# KON-SU260.net
KiCad netlist of a schematic drawn in EAGLE
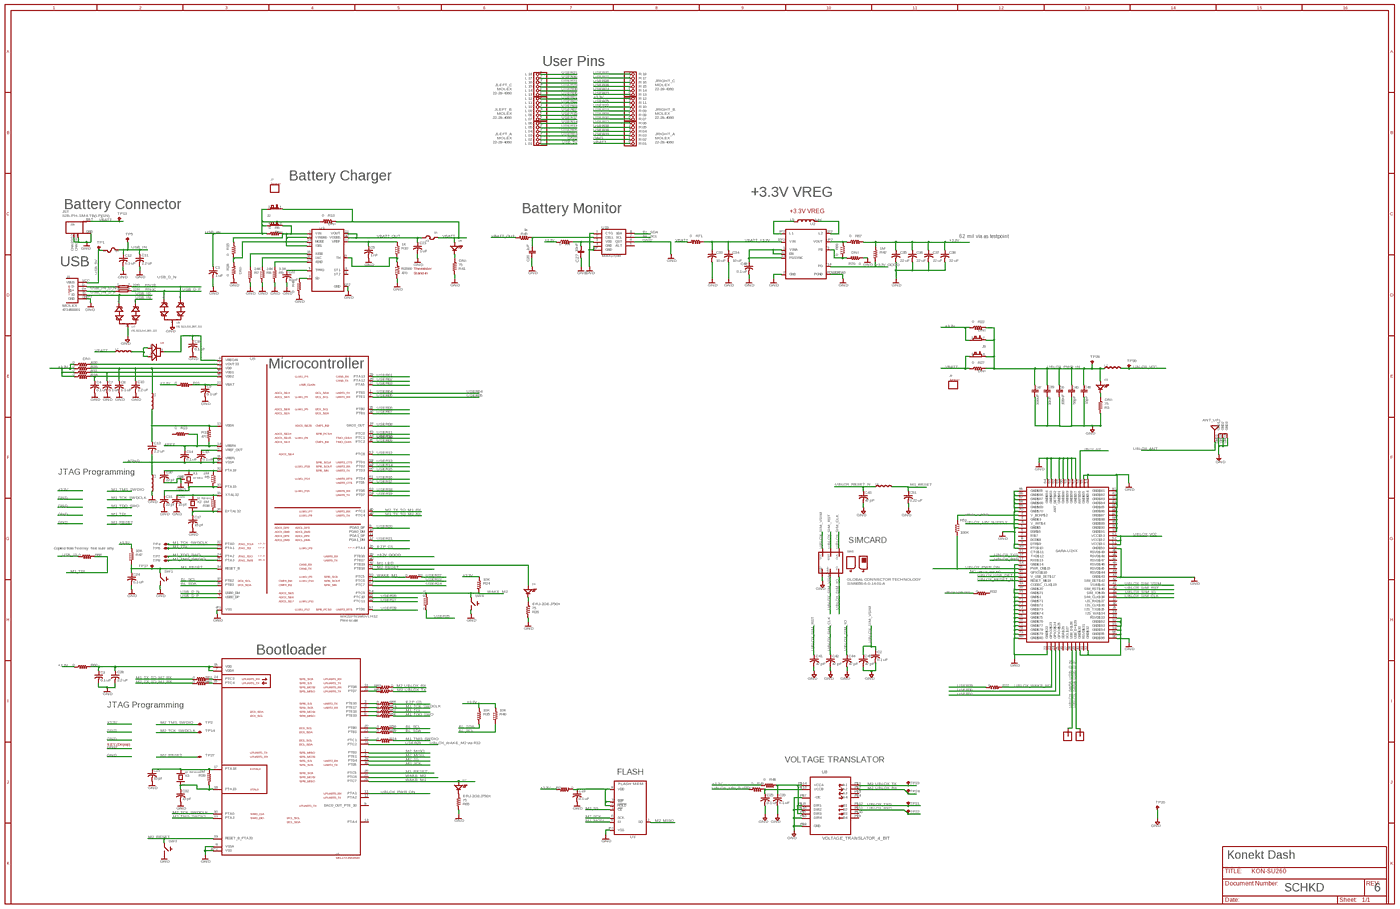
[diagram p0: schematic, sheet 1, overview]
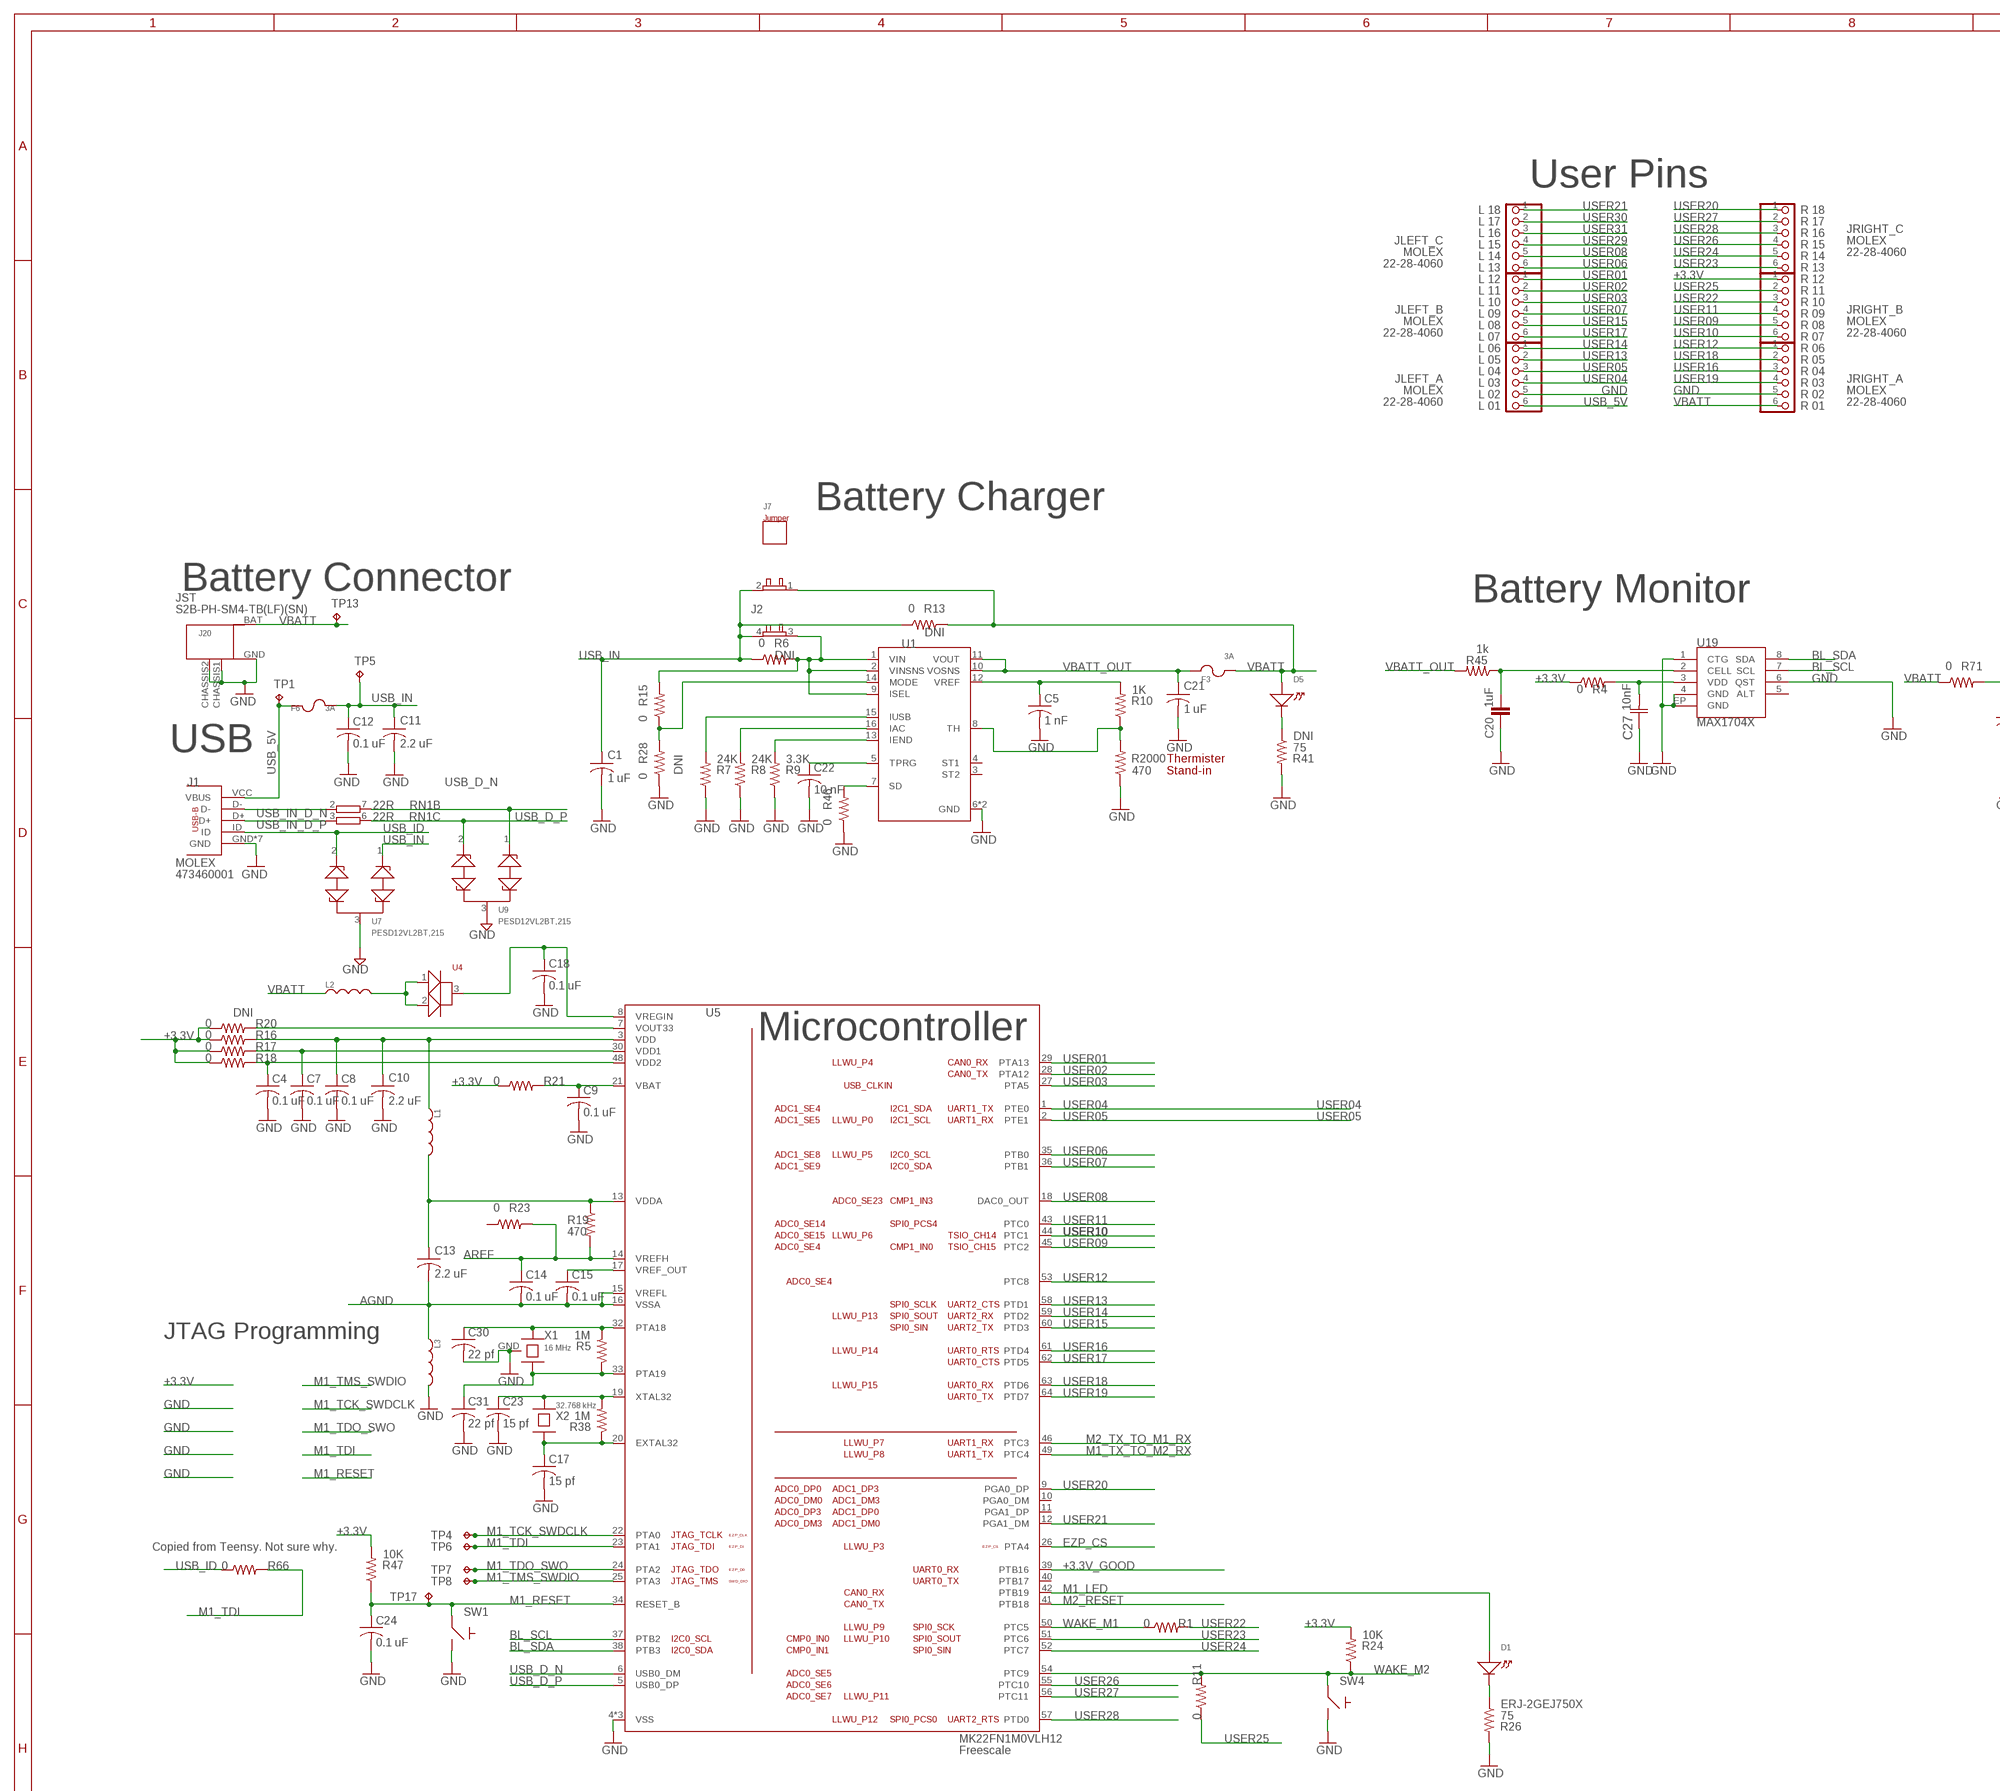
[diagram p1: schematic, sheet 1, part 1 of 4]
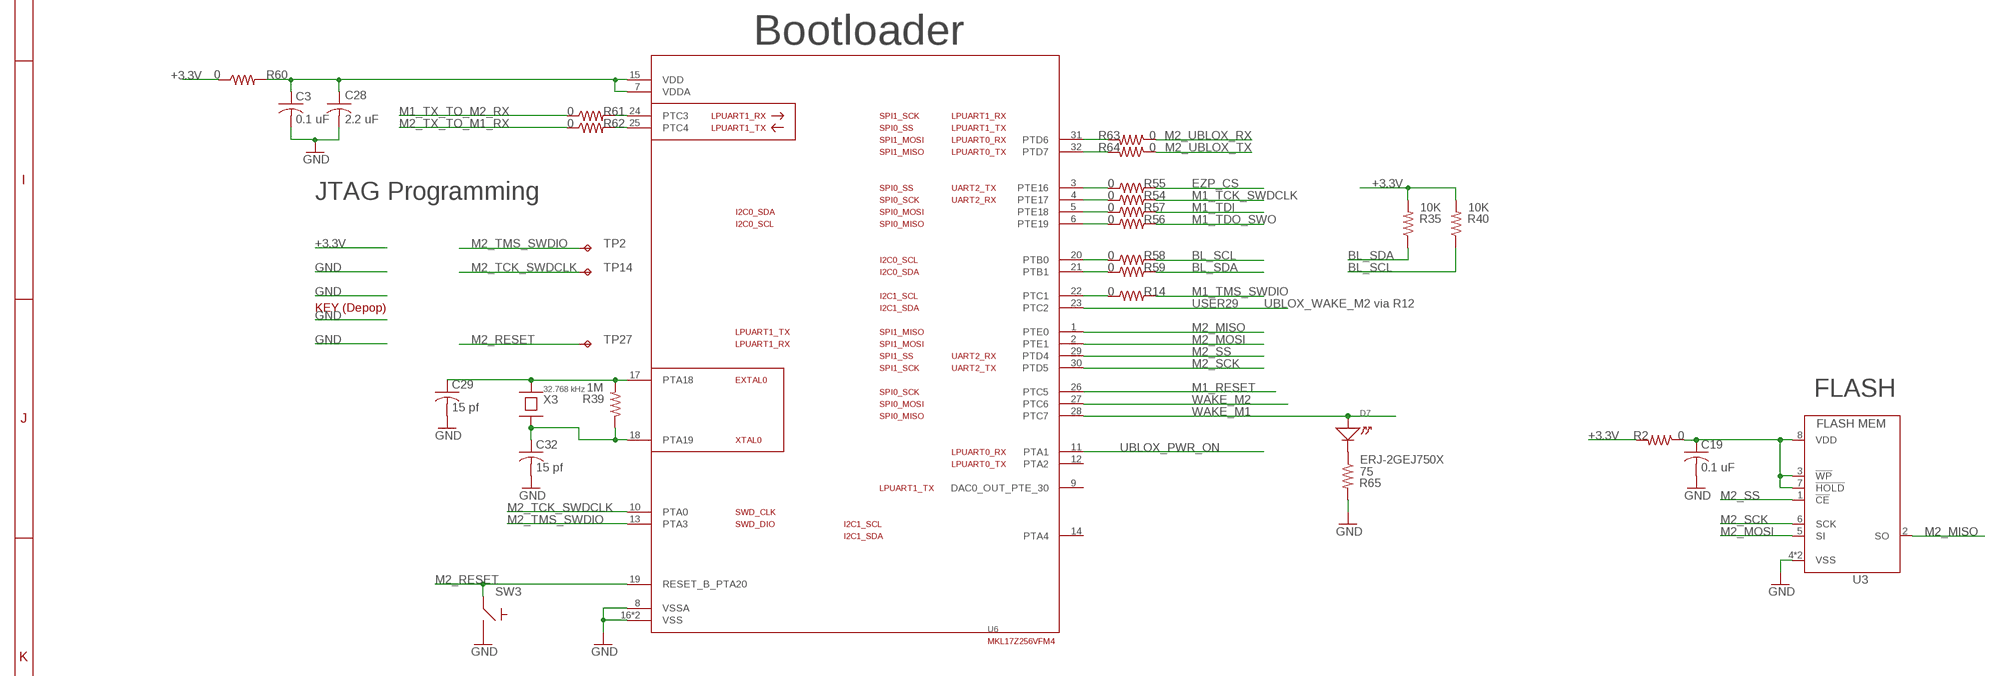
[diagram p2: schematic, sheet 1, part 2 of 4]
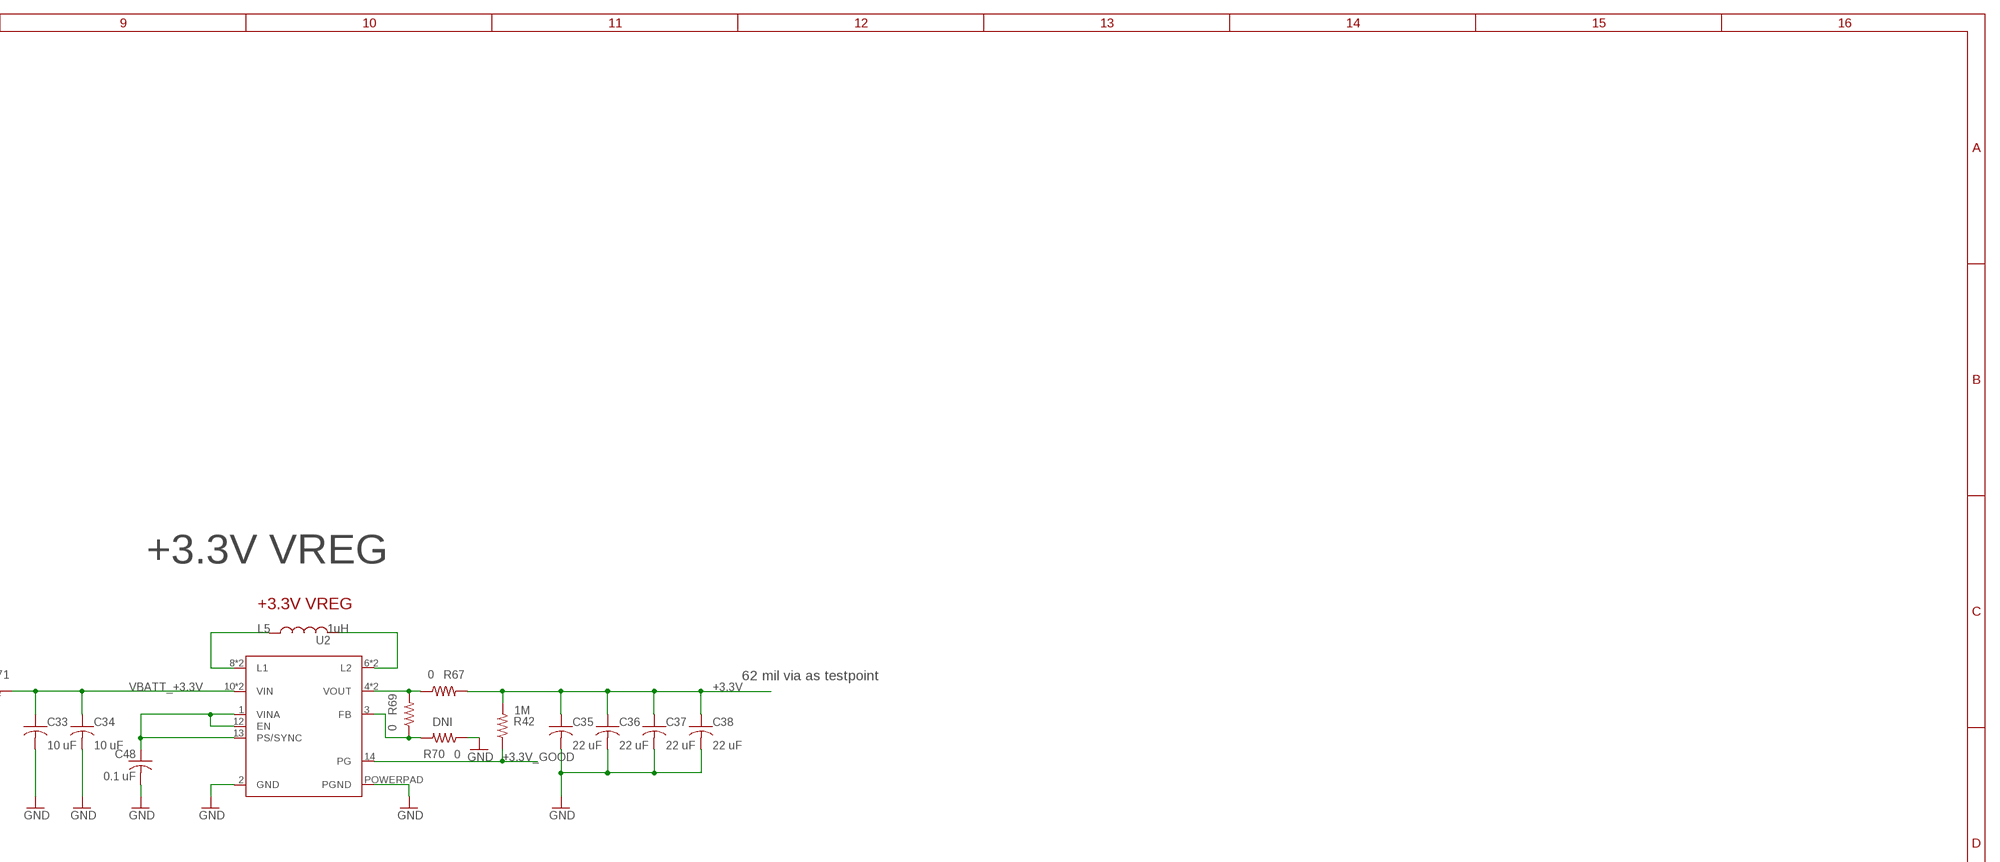
[diagram p3: schematic, sheet 1, part 3 of 4]
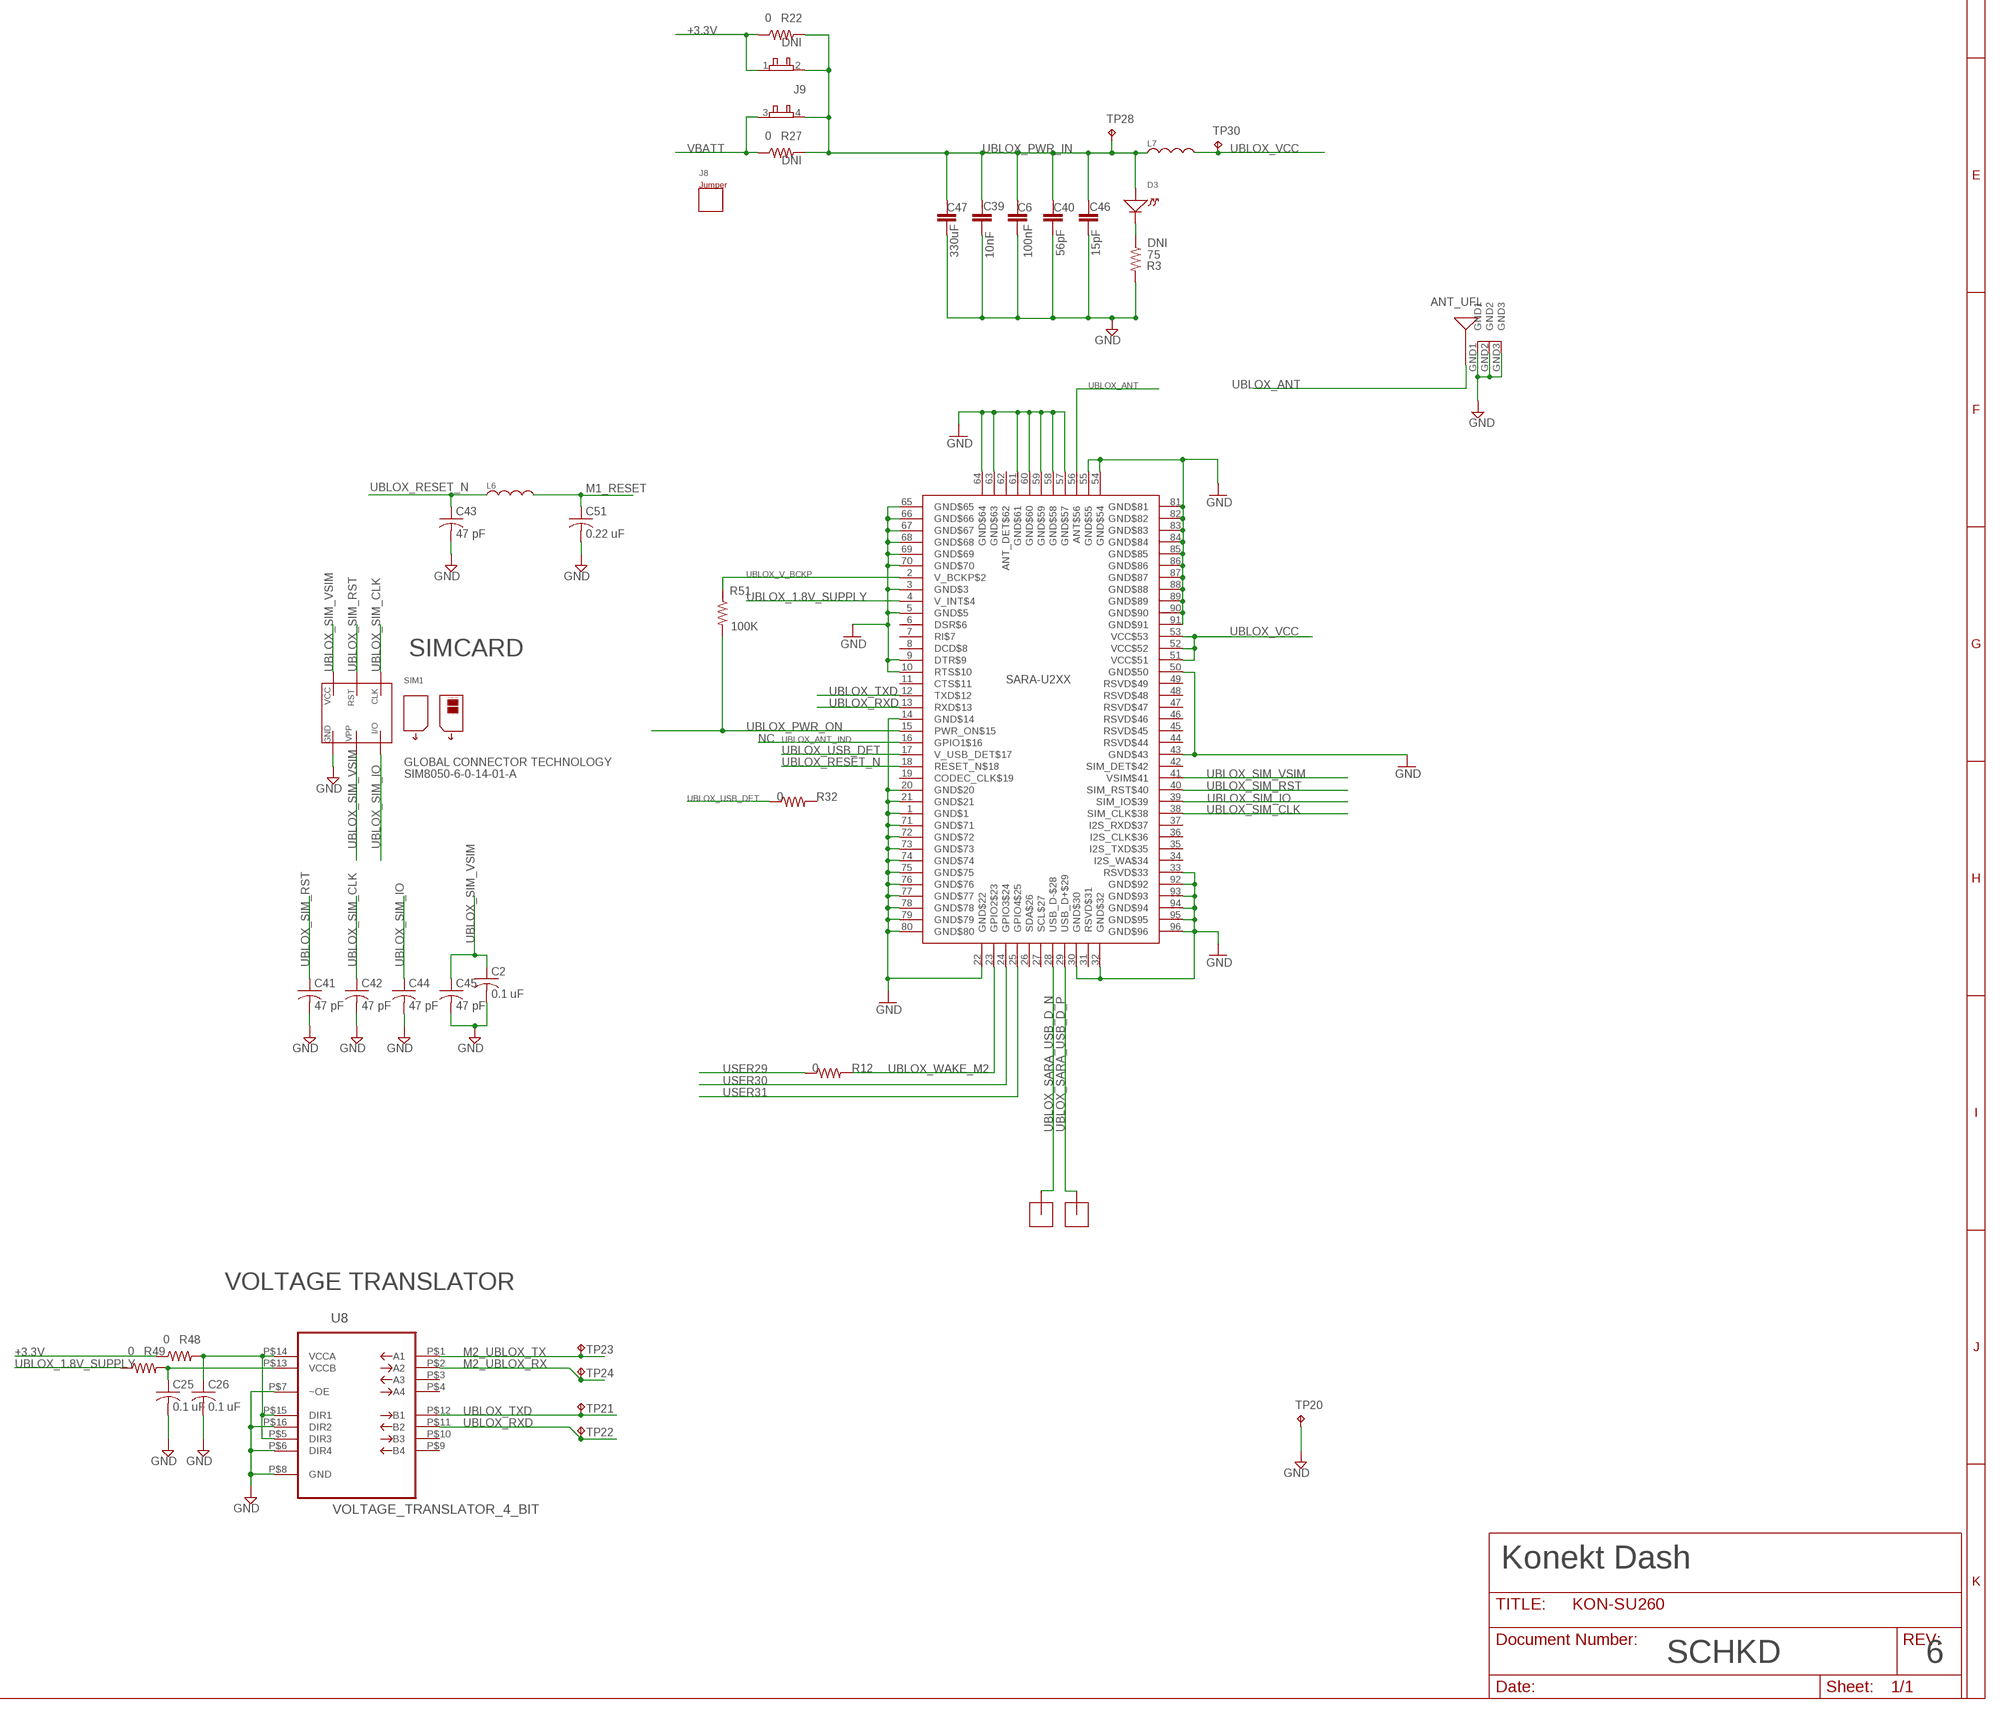
[diagram p4: schematic, sheet 1, part 4 of 4]

(export (version "E")
  (design (tool "Eeschema 10.0.6"))
  (components
    (comp (ref "ANT_UFL")
      (value "ANT-A-1JB")
      (footprint "eagle-import:UFL")
      (fields (field (name "MFG") "AMPHENOL") (field (name "PARTNUM") "A-1JB"))
      (libsource (lib "eagle-import") (part "ANT-A-1JB"))
    )
    (comp (ref "C1")
      (value "1 uF")
      (footprint "eagle-import:C0603")
      (fields (field (name "MFG") "MURATA") (field (name "MPN") "GRM188R71C105KA12D"))
      (libsource (lib "eagle-import") (part "resistor_C-USC0603"))
    )
    (comp (ref "C2")
      (value "0.1 uF")
      (footprint "eagle-import:C0402")
      (fields (field (name "MFG") "MURATA") (field (name "MPN") "GRM155R61C104KA88D"))
      (libsource (lib "eagle-import") (part "C-USC0402"))
    )
    (comp (ref "C3")
      (value "0.1 uF")
      (footprint "eagle-import:C0402")
      (fields (field (name "MFG") "MURATA") (field (name "MPN") "GRM155R61C104KA88D"))
      (libsource (lib "eagle-import") (part "C-USC0402"))
    )
    (comp (ref "C4")
      (value "0.1 uF")
      (footprint "eagle-import:C0402")
      (fields (field (name "MFG") "MURATA") (field (name "MPN") "GRM155R61C104KA88D"))
      (libsource (lib "eagle-import") (part "C-USC0402"))
    )
    (comp (ref "C5")
      (value "1 nF")
      (footprint "eagle-import:C0402")
      (fields (field (name "MFG") "MURATA") (field (name "MPN") "GRM319R71H102KA01D"))
      (libsource (lib "eagle-import") (part "resistor_C-USC0402"))
    )
    (comp (ref "C6")
      (value "100nF")
      (footprint "eagle-import:0402-CAP@1")
      (description "Capacitor, 100nF, 25V, 10%")
      (fields
        (field (name "MANUFACTURER") "Murata")
        (field (name "MFG") "MURATA")
        (field (name "MPN") "GRM155R71C104KA88D")
      )
      (libsource (lib "eagle-import") (part "CAP0402-CAP"))
    )
    (comp (ref "C7")
      (value "0.1 uF")
      (footprint "eagle-import:C0402")
      (fields (field (name "MFG") "MURATA") (field (name "MPN") "GRM155R61C104KA88D"))
      (libsource (lib "eagle-import") (part "C-USC0402"))
    )
    (comp (ref "C8")
      (value "0.1 uF")
      (footprint "eagle-import:C0402")
      (fields (field (name "MFG") "MURATA") (field (name "MPN") "GRM155R61C104KA88D"))
      (libsource (lib "eagle-import") (part "C-USC0402"))
    )
    (comp (ref "C9")
      (value "0.1 uF")
      (footprint "eagle-import:C0402")
      (fields (field (name "MFG") "AVX/ELCO") (field (name "MPN") "0402YC104KAT2A"))
      (libsource (lib "eagle-import") (part "C-USC0402"))
    )
    (comp (ref "C10")
      (value "2.2 uF")
      (footprint "eagle-import:C0603")
      (fields (field (name "MFG") "SAMSUNG") (field (name "MPN") "CL10A225MQ8NNNC"))
      (libsource (lib "eagle-import") (part "resistor_C-USC0603"))
    )
    (comp (ref "C11")
      (value "2.2 uF")
      (footprint "eagle-import:C0603")
      (fields (field (name "MFG") "SAMSUNG") (field (name "MPN") "CL10A225MQ8NNNC"))
      (libsource (lib "eagle-import") (part "resistor_C-USC0603"))
    )
    (comp (ref "C12")
      (value "0.1 uF")
      (footprint "eagle-import:C0603")
      (fields (field (name "MFG") "AVX") (field (name "MPN") "0603YC104KAT2A"))
      (libsource (lib "eagle-import") (part "resistor_C-USC0603"))
    )
    (comp (ref "C13")
      (value "2.2 uF")
      (footprint "eagle-import:C0603")
      (fields (field (name "MFG") "SAMSUNG") (field (name "MPN") "CL10A225MQ8NNNC"))
      (libsource (lib "eagle-import") (part "resistor_C-USC0603"))
    )
    (comp (ref "C14")
      (value "0.1 uF")
      (footprint "eagle-import:C0402")
      (fields (field (name "MFG") "MURATA") (field (name "MPN") "GRM155R61C104KA88D"))
      (libsource (lib "eagle-import") (part "C-USC0402"))
    )
    (comp (ref "C15")
      (value "0.1 uF")
      (footprint "eagle-import:C0402")
      (fields (field (name "MFG") "MURATA") (field (name "MPN") "GRM155R61C104KA88D"))
      (libsource (lib "eagle-import") (part "C-USC0402"))
    )
    (comp (ref "C17")
      (value "15 pf")
      (footprint "eagle-import:C0402")
      (fields (field (name "MFG") "AVX/ELCO") (field (name "MPN") "04025A150JAT2A"))
      (libsource (lib "eagle-import") (part "C-USC0402"))
    )
    (comp (ref "C18")
      (value "0.1 uF")
      (footprint "eagle-import:C0402")
      (fields (field (name "MFG") "MURATA") (field (name "MPN") "GRM155R61C104KA88D"))
      (libsource (lib "eagle-import") (part "C-USC0402"))
    )
    (comp (ref "C19")
      (value "0.1 uF")
      (footprint "eagle-import:C0402")
      (fields (field (name "MFG") "MURATA") (field (name "MPN") "GRM155R61C104KA88D"))
      (libsource (lib "eagle-import") (part "C-USC0402"))
    )
    (comp (ref "C20")
      (value "1uF")
      (footprint "eagle-import:0402-CAP")
      (description "Capacitor, 10%, 50V")
      (fields
        (field (name "MFG") "AVX")
        (field (name "MPN") "04026D105KAT2A")
        (field (name "TOLERANCE") "10%")
        (field (name "VOLTAGE") "50V")
      )
      (libsource (lib "eagle-import") (part "CAPACITOR0402"))
    )
    (comp (ref "C21")
      (value "1 uF")
      (footprint "eagle-import:C0603")
      (fields (field (name "MFG") "MURATA") (field (name "MPN") "GRM188R71C105KA12D"))
      (libsource (lib "eagle-import") (part "resistor_C-USC0603"))
    )
    (comp (ref "C22")
      (value "10 nF")
      (footprint "eagle-import:C0402")
      (fields (field (name "MFG") "MURATA") (field (name "MPN") "GRM155R71C103KA01D"))
      (libsource (lib "eagle-import") (part "resistor_C-USC0402"))
    )
    (comp (ref "C23")
      (value "15 pf")
      (footprint "eagle-import:C0402")
      (fields (field (name "MFG") "AVX/ELCO") (field (name "MPN") "04025A150JAT2A"))
      (libsource (lib "eagle-import") (part "C-USC0402"))
    )
    (comp (ref "C24")
      (value "0.1 uF")
      (footprint "eagle-import:C0402")
      (fields (field (name "MFG") "MURATA") (field (name "MPN") "GRM155R61C104KA88D"))
      (libsource (lib "eagle-import") (part "C-USC0402"))
    )
    (comp (ref "C25")
      (value "0.1 uF")
      (footprint "eagle-import:C0402")
      (fields (field (name "MFG") "MURATA") (field (name "MPN") "GRM155R61C104KA88D104KAT2A"))
      (libsource (lib "eagle-import") (part "C-USC0402"))
    )
    (comp (ref "C26")
      (value "0.1 uF")
      (footprint "eagle-import:C0402")
      (fields (field (name "MFG") "MURATA") (field (name "MPN") "GRM155R61C104KA88D"))
      (libsource (lib "eagle-import") (part "C-USC0402"))
    )
    (comp (ref "C27")
      (value "10nF")
      (footprint "eagle-import:CAPC1005X60N")
      (description "CAPACITOR, 0402")
      (fields (field (name "MPN") "GRM155R71E103KA01D") (field (name "TOLERANCE") "±10%"))
      (libsource (lib "eagle-import") (part "GRM155R71E103KA01D"))
    )
    (comp (ref "C28")
      (value "2.2 uF")
      (footprint "eagle-import:C0603")
      (fields (field (name "MFG") "SAMSUNG") (field (name "MPN") "CL10A225MQ8NNNC"))
      (libsource (lib "eagle-import") (part "resistor_C-USC0603"))
    )
    (comp (ref "C29")
      (value "15 pf")
      (footprint "eagle-import:C0402")
      (fields (field (name "MFG") "AVX/ELCO") (field (name "MPN") "04025A150JAT2A"))
      (libsource (lib "eagle-import") (part "C-USC0402"))
    )
    (comp (ref "C30")
      (value "22 pf")
      (footprint "eagle-import:C0402")
      (fields (field (name "MFG") "AVX/ELCO") (field (name "MPN") "04025A220JAT2A"))
      (libsource (lib "eagle-import") (part "C-USC0402"))
    )
    (comp (ref "C31")
      (value "22 pf")
      (footprint "eagle-import:C0402")
      (fields (field (name "MFG") "AVX/ELCO") (field (name "MPN") "04025A220JAT2A"))
      (libsource (lib "eagle-import") (part "C-USC0402"))
    )
    (comp (ref "C32")
      (value "15 pf")
      (footprint "eagle-import:C0402")
      (fields (field (name "MFG") "AVX/ELCO") (field (name "MPN") "04025A150JAT2A"))
      (libsource (lib "eagle-import") (part "C-USC0402"))
    )
    (comp (ref "C33")
      (value "10 uF")
      (footprint "eagle-import:C0603")
      (fields (field (name "MFG") "MURATA") (field (name "MPN") "GRM188R60J106ME84D"))
      (libsource (lib "eagle-import") (part "resistor_C-USC0603"))
    )
    (comp (ref "C34")
      (value "10 uF")
      (footprint "eagle-import:C0603")
      (fields (field (name "MFG") "MURATA") (field (name "MPN") "GRM188R60J106ME84D"))
      (libsource (lib "eagle-import") (part "resistor_C-USC0603"))
    )
    (comp (ref "C35")
      (value "22 uF")
      (footprint "eagle-import:C0603")
      (fields (field (name "MFG") "MURATA") (field (name "MPN") "GRM188R60J226MEA0D"))
      (libsource (lib "eagle-import") (part "resistor_C-USC0603"))
    )
    (comp (ref "C36")
      (value "22 uF")
      (footprint "eagle-import:C0603")
      (fields (field (name "MFG") "MURATA") (field (name "MPN") "GRM188R60J226MEA0D"))
      (libsource (lib "eagle-import") (part "resistor_C-USC0603"))
    )
    (comp (ref "C37")
      (value "22 uF")
      (footprint "eagle-import:C0603")
      (fields (field (name "MFG") "MURATA") (field (name "MPN") "GRM188R60J226MEA0D"))
      (libsource (lib "eagle-import") (part "resistor_C-USC0603"))
    )
    (comp (ref "C38")
      (value "22 uF")
      (footprint "eagle-import:C0603")
      (fields (field (name "MFG") "MURATA") (field (name "MPN") "GRM188R60J226MEA0D"))
      (libsource (lib "eagle-import") (part "resistor_C-USC0603"))
    )
    (comp (ref "C39")
      (value "10nF")
      (footprint "eagle-import:0402-CAP@1")
      (description "Capacitor, 10nF, 25V, 10%")
      (fields
        (field (name "MANUFACTURER") "AVX")
        (field (name "MFG") "MURATA")
        (field (name "MPN") "GRM155R71E103KA01D")
      )
      (libsource (lib "eagle-import") (part "CAP0402-CAP"))
    )
    (comp (ref "C40")
      (value "56pF")
      (footprint "eagle-import:0402-CAP@1")
      (description "Capacitor, 56pF, 50V, 5%")
      (fields
        (field (name "MANUFACTURER") "Kemet")
        (field (name "MFG") "KEMET")
        (field (name "MPN") "C0402C560J5GACTU")
      )
      (libsource (lib "eagle-import") (part "CAP0402-CAP"))
    )
    (comp (ref "C41")
      (value "47 pF")
      (footprint "eagle-import:C0402")
      (fields (field (name "MFG") "AVX") (field (name "MPN") "04025A470JAT2A"))
      (libsource (lib "eagle-import") (part "resistor_C-USC0402"))
    )
    (comp (ref "C42")
      (value "47 pF")
      (footprint "eagle-import:C0402")
      (fields (field (name "MFG") "AVX") (field (name "MPN") "04025A470JAT2A"))
      (libsource (lib "eagle-import") (part "resistor_C-USC0402"))
    )
    (comp (ref "C43")
      (value "47 pF")
      (footprint "eagle-import:C0402")
      (fields (field (name "MFG") "AVX") (field (name "MPN") "04025A470JAT2A"))
      (libsource (lib "eagle-import") (part "resistor_C-USC0402"))
    )
    (comp (ref "C44")
      (value "47 pF")
      (footprint "eagle-import:C0402")
      (fields (field (name "MFG") "AVX") (field (name "MPN") "04025A470JAT2A"))
      (libsource (lib "eagle-import") (part "resistor_C-USC0402"))
    )
    (comp (ref "C45")
      (value "47 pF")
      (footprint "eagle-import:C0402")
      (fields (field (name "MFG") "AVX") (field (name "MPN") "04025A470JAT2A"))
      (libsource (lib "eagle-import") (part "resistor_C-USC0402"))
    )
    (comp (ref "C46")
      (value "15pF")
      (footprint "eagle-import:0402-CAP@1")
      (description "Capacitor, 15pF, 50V, 5%")
      (fields
        (field (name "MANUFACTURER") "Kemet")
        (field (name "MFG") "KEMET")
        (field (name "MPN") "C0402C150J5GACTU")
      )
      (libsource (lib "eagle-import") (part "CAP0402-CAP"))
    )
    (comp (ref "C47")
      (value "330uF")
      (footprint "eagle-import:1210-CAP")
      (description "Capacitor, 330uF, 6.3V, 20%")
      (fields
        (field (name "MANUFACTURER") "AVX")
        (field (name "MFG") "AVX")
        (field (name "MPN") "F950J337MBAAQ2")
      )
      (libsource (lib "eagle-import") (part "CAP1210-CAP"))
    )
    (comp (ref "C48")
      (value "0.1 uF")
      (footprint "eagle-import:C0402")
      (fields (field (name "MFG") "MURATA") (field (name "MPN") "GRM155R61C104KA88D"))
      (libsource (lib "eagle-import") (part "C-USC0402"))
    )
    (comp (ref "C51")
      (value "0.22 uF")
      (footprint "eagle-import:C0402")
      (fields (field (name "MFG") "MURATA") (field (name "MPN") "GRM155R60J224KE01D"))
      (libsource (lib "eagle-import") (part "C-USC0402"))
    )
    (comp (ref "D1")
      (value "LED_0402_VLMW")
      (footprint "eagle-import:LED_0402_VISHAY_VLMW")
      (fields (field (name "MFG") "VISHAY") (field (name "MPN") "VLMW1500-GS08"))
      (libsource (lib "eagle-import") (part "LED_0402_VLMW"))
    )
    (comp (ref "D3")
      (value "LED_0402_VLMW")
      (footprint "eagle-import:LED_0402_VISHAY_VLMW")
      (fields (field (name "MFG") "VISHAY") (field (name "MPN") "VLMW1500-GS08"))
      (libsource (lib "eagle-import") (part "LED_0402_VLMW"))
    )
    (comp (ref "D5")
      (value "LED_0402_VLMW")
      (footprint "eagle-import:LED_0402_VISHAY_VLMW")
      (fields (field (name "MFG") "VISHAY") (field (name "MPN") "VLMW1500-GS08"))
      (libsource (lib "eagle-import") (part "LED_0402_VLMW"))
    )
    (comp (ref "D7")
      (value "LED_0402_VLMW")
      (footprint "eagle-import:LED_0402_VISHAY_VLMW")
      (fields (field (name "MFG") "VISHAY") (field (name "MPN") "VLMW1500-GS08"))
      (libsource (lib "eagle-import") (part "LED_0402_VLMW"))
    )
    (comp (ref "F3")
      (value "3A")
      (footprint "eagle-import:R0603")
      (fields (field (name "MFG") "Bourns") (field (name "MPN") "SF-0603S300-2"))
      (libsource (lib "eagle-import") (part "FUSE_0603"))
    )
    (comp (ref "F6")
      (value "3A")
      (footprint "eagle-import:R0603")
      (fields (field (name "MFG") "Bourns") (field (name "MPN") "SF-0603S300-2"))
      (libsource (lib "eagle-import") (part "FUSE_0603"))
    )
    (comp (ref "J1")
      (value "USB_MICRO_B_MOLEX_473460001")
      (footprint "eagle-import:USB_MICRO_MOLEX_473460001")
      (fields
        (field (name "MFG") "MOLEX")
        (field (name "PARTNUM") "473460001")
        (field (name "MPN") "473460001")
      )
      (libsource (lib "eagle-import") (part "USB_MICRO_B_MOLEX_473460001"))
    )
    (comp (ref "J2")
      (value "CON_JUMPER_1.27_2X2")
      (footprint "eagle-import:FCI_CON_1.27_2X2")
      (fields (field (name "MFG") "FCI") (field (name "MPN") "20021121-00004C4LF"))
      (libsource (lib "eagle-import") (part "CON_JUMPER_1.27_2X2"))
    )
    (comp (ref "J7")
      (value "JUMPER_1.27MM")
      (footprint "eagle-import:NOTHING")
      (fields (field (name "MFG") "HARWIN") (field (name "MPN") "M50-1920005"))
      (libsource (lib "eagle-import") (part "JUMPER_1.27MM"))
    )
    (comp (ref "J8")
      (value "JUMPER_1.27MM")
      (footprint "eagle-import:NOTHING")
      (fields (field (name "MFG") "HARWIN") (field (name "MPN") "M50-1920005"))
      (libsource (lib "eagle-import") (part "JUMPER_1.27MM"))
    )
    (comp (ref "J9")
      (value "CON_JUMPER_1.27_2X2")
      (footprint "eagle-import:FCI_CON_1.27_2X2")
      (fields (field (name "MFG") "FCI") (field (name "MPN") "20021121-00004C4LF"))
      (libsource (lib "eagle-import") (part "CON_JUMPER_1.27_2X2"))
    )
    (comp (ref "J20")
      (value "BAT_TERM")
      (footprint "eagle-import:JST-PH-2")
      (fields
        (field (name "MFG") "JST")
        (field (name "PARTNUM") "S2B-PH-SM4-TB(LF)(SN)")
        (field (name "MFG_1") "JST")
        (field (name "MPN") "S2B-PH-SM4-TB(LF)(SN)")
        (field (name "PARTNUM_1") "S2B-PH-SM4-TB(LF)(SN)")
      )
      (libsource (lib "eagle-import") (part "BAT_TERM"))
    )
    (comp (ref "JLEFT_A")
      (value "PINHD-1X6")
      (footprint "eagle-import:1X06")
      (fields (field (name "MFG") "MOLEX") (field (name "MPN") "22-28-4060"))
      (libsource (lib "eagle-import") (part "PINHD-1X6"))
    )
    (comp (ref "JLEFT_B")
      (value "PINHD-1X6")
      (footprint "eagle-import:1X06")
      (fields (field (name "MFG") "MOLEX") (field (name "MPN") "22-28-4060"))
      (libsource (lib "eagle-import") (part "PINHD-1X6"))
    )
    (comp (ref "JLEFT_C")
      (value "PINHD-1X6")
      (footprint "eagle-import:1X06")
      (fields (field (name "MFG") "MOLEX") (field (name "MPN") "22-28-4060"))
      (libsource (lib "eagle-import") (part "PINHD-1X6"))
    )
    (comp (ref "JRIGHT_A")
      (value "PINHD-1X6")
      (footprint "eagle-import:1X06")
      (fields (field (name "MFG") "MOLEX") (field (name "MPN") "22-28-4060"))
      (libsource (lib "eagle-import") (part "PINHD-1X6"))
    )
    (comp (ref "JRIGHT_B")
      (value "PINHD-1X6")
      (footprint "eagle-import:1X06")
      (fields (field (name "MFG") "MOLEX") (field (name "MPN") "22-28-4060"))
      (libsource (lib "eagle-import") (part "PINHD-1X6"))
    )
    (comp (ref "JRIGHT_C")
      (value "PINHD-1X6")
      (footprint "eagle-import:1X06")
      (fields (field (name "MFG") "MOLEX") (field (name "MPN") "22-28-4060"))
      (libsource (lib "eagle-import") (part "PINHD-1X6"))
    )
    (comp (ref "L1")
      (value "INDUCTOR_0603")
      (footprint "eagle-import:R0603$1")
      (fields (field (name "MFG") "Murata") (field (name "MPN") "BLM18AG121SN1D"))
      (libsource (lib "eagle-import") (part "INDUCTOR_0603"))
    )
    (comp (ref "L2")
      (value "INDUCTOR_0603")
      (footprint "eagle-import:R0603$1")
      (fields (field (name "MFG") "TDK") (field (name "MPN") "MPZ1608S221A"))
      (libsource (lib "eagle-import") (part "INDUCTOR_0603"))
    )
    (comp (ref "L3")
      (value "INDUCTOR_0603")
      (footprint "eagle-import:R0603$1")
      (fields (field (name "MFG") "Murata") (field (name "MPN") "BLM18AG121SN1D"))
      (libsource (lib "eagle-import") (part "INDUCTOR_0603"))
    )
    (comp (ref "L5")
      (value "1uH")
      (footprint "eagle-import:COILCRAFT_XFL4020")
      (fields (field (name "MFG") "COILCRAFT") (field (name "MPN") "XFL4020-102MEC"))
      (libsource (lib "eagle-import") (part "INDUCTOR_1UH_XFL4020-102MEC"))
    )
    (comp (ref "L6")
      (value "INDUCTOR_0603")
      (footprint "eagle-import:R0603$1")
      (fields (field (name "MFG") "TDK") (field (name "MPN") "MPZ1608S221A"))
      (libsource (lib "eagle-import") (part "INDUCTOR_0603"))
    )
    (comp (ref "L7")
      (value "INDUCTOR_0603")
      (footprint "eagle-import:R0603$1")
      (fields (field (name "MFG") "MURATA") (field (name "MPN") "BLM18EG221SN1D"))
      (libsource (lib "eagle-import") (part "INDUCTOR_0603"))
    )
    (comp (ref "R1")
      (value "0")
      (footprint "eagle-import:0402-RES")
      (description "Resistor, 1%, 0.125W")
      (fields
        (field (name "MANUFACTURER") "Panasonic")
        (field (name "MFG") "PANASONIC")
        (field (name "MPN") "ERJ-2GE0R00X")
      )
      (libsource (lib "eagle-import") (part "RESISTOR0402-RES"))
    )
    (comp (ref "R2")
      (value "0")
      (footprint "eagle-import:0402-RES")
      (description "Resistor, 1%, 0.125W")
      (fields
        (field (name "MANUFACTURER") "Panasonic")
        (field (name "MFG") "PANASONIC")
        (field (name "MPN") "ERJ-2GE0R00X")
      )
      (libsource (lib "eagle-import") (part "RESISTOR0402-RES"))
    )
    (comp (ref "R3")
      (value "75")
      (footprint "eagle-import:0402-RES")
      (description "Resistor, 1%, 0.125W")
      (fields
        (field (name "MANUFACTURER") "Panasonic")
        (field (name "MFG") "PANASONIC")
        (field (name "MPN") "DNI")
      )
      (libsource (lib "eagle-import") (part "RESISTOR0402-RES"))
    )
    (comp (ref "R4")
      (value "0")
      (footprint "eagle-import:0402-RES")
      (description "Resistor, 1%, 0.125W")
      (fields
        (field (name "MANUFACTURER") "Panasonic")
        (field (name "MFG") "PANASONIC")
        (field (name "MPN") "ERJ-2GE0R00X")
      )
      (libsource (lib "eagle-import") (part "RESISTOR0402-RES"))
    )
    (comp (ref "R5")
      (value "1M")
      (footprint "eagle-import:0402-RES")
      (description "Resistor, 1%, 0.125W")
      (fields
        (field (name "MANUFACTURER") "Yaego")
        (field (name "MFG") "YAEGO")
        (field (name "MPN") "RC0402JR-071ML")
      )
      (libsource (lib "eagle-import") (part "RESISTOR0402-RES"))
    )
    (comp (ref "R6")
      (value "0")
      (footprint "eagle-import:0402-RES")
      (description "Resistor, 1%, 0.125W")
      (fields
        (field (name "MANUFACTURER") "Panasonic")
        (field (name "MFG") "PANASONIC")
        (field (name "MPN") "DNI")
      )
      (libsource (lib "eagle-import") (part "RESISTOR0402-RES"))
    )
    (comp (ref "R7")
      (value "24K")
      (footprint "eagle-import:0402-RES")
      (description "Resistor, 1%, 0.125W")
      (fields
        (field (name "MANUFACTURER") "Yaego")
        (field (name "MFG") "YAEGO")
        (field (name "MPN") "RC0402JR-0724KL")
      )
      (libsource (lib "eagle-import") (part "RESISTOR0402-RES"))
    )
    (comp (ref "R8")
      (value "24K")
      (footprint "eagle-import:0402-RES")
      (description "Resistor, 1%, 0.125W")
      (fields
        (field (name "MANUFACTURER") "Yaego")
        (field (name "MFG") "YAEGO")
        (field (name "MPN") "RC0402JR-0724KL")
      )
      (libsource (lib "eagle-import") (part "RESISTOR0402-RES"))
    )
    (comp (ref "R9")
      (value "3.3K")
      (footprint "eagle-import:0402-RES")
      (description "Resistor, 1%, 0.125W")
      (fields
        (field (name "MANUFACTURER") "Yaego")
        (field (name "MFG") "YAEGO")
        (field (name "MPN") "RC0402JR-073K3L")
      )
      (libsource (lib "eagle-import") (part "RESISTOR0402-RES"))
    )
    (comp (ref "R10")
      (value "1K")
      (footprint "eagle-import:0402-RES")
      (description "Resistor, 1%, 0.125W")
      (fields
        (field (name "MANUFACTURER") "Yaego")
        (field (name "MFG") "YAEGO")
        (field (name "MPN") "RC0402JR-071KL")
      )
      (libsource (lib "eagle-import") (part "RESISTOR0402-RES"))
    )
    (comp (ref "R11")
      (value "0")
      (footprint "eagle-import:0402-RES")
      (description "Resistor, 1%, 0.125W")
      (fields
        (field (name "MANUFACTURER") "Panasonic")
        (field (name "MFG") "PANASONIC")
        (field (name "MPN") "ERJ-2GE0R00X")
      )
      (libsource (lib "eagle-import") (part "RESISTOR0402-RES"))
    )
    (comp (ref "R12")
      (value "0")
      (footprint "eagle-import:0402-RES")
      (description "Resistor, 1%, 0.125W")
      (fields
        (field (name "MANUFACTURER") "Panasonic")
        (field (name "MFG") "PANASONIC")
        (field (name "MPN") "ERJ-2GE0R00X")
      )
      (libsource (lib "eagle-import") (part "RESISTOR0402-RES"))
    )
    (comp (ref "R13")
      (value "0")
      (footprint "eagle-import:0402-RES")
      (description "Resistor, 1%, 0.125W")
      (fields
        (field (name "MANUFACTURER") "Panasonic")
        (field (name "MFG") "PANASONIC")
        (field (name "MPN") "DNI")
      )
      (libsource (lib "eagle-import") (part "RESISTOR0402-RES"))
    )
    (comp (ref "R14")
      (value "0")
      (footprint "eagle-import:0402-RES")
      (description "Resistor, 1%, 0.125W")
      (fields
        (field (name "MANUFACTURER") "Panasonic")
        (field (name "MFG") "PANASONIC")
        (field (name "MPN") "ERJ-2GE0R00X")
      )
      (libsource (lib "eagle-import") (part "RESISTOR0402-RES"))
    )
    (comp (ref "R15")
      (value "0")
      (footprint "eagle-import:0402-RES")
      (description "Resistor, 1%, 0.125W")
      (fields
        (field (name "MANUFACTURER") "Panasonic")
        (field (name "MFG") "PANASONIC")
        (field (name "MPN") "ERJ-2GE0R00X")
      )
      (libsource (lib "eagle-import") (part "RESISTOR0402-RES"))
    )
    (comp (ref "R16")
      (value "0")
      (footprint "eagle-import:0402-RES")
      (description "Resistor, 1%, 0.125W")
      (fields
        (field (name "MANUFACTURER") "Panasonic")
        (field (name "MFG") "PANASONIC")
        (field (name "MPN") "ERJ-2GE0R00X")
      )
      (libsource (lib "eagle-import") (part "RESISTOR0402-RES"))
    )
    (comp (ref "R17")
      (value "0")
      (footprint "eagle-import:0402-RES")
      (description "Resistor, 1%, 0.125W")
      (fields
        (field (name "MANUFACTURER") "Panasonic")
        (field (name "MFG") "PANASONIC")
        (field (name "MPN") "ERJ-2GE0R00X")
      )
      (libsource (lib "eagle-import") (part "RESISTOR0402-RES"))
    )
    (comp (ref "R18")
      (value "0")
      (footprint "eagle-import:0402-RES")
      (description "Resistor, 1%, 0.125W")
      (fields
        (field (name "MANUFACTURER") "Panasonic")
        (field (name "MFG") "PANASONIC")
        (field (name "MPN") "ERJ-2GE0R00X")
      )
      (libsource (lib "eagle-import") (part "RESISTOR0402-RES"))
    )
    (comp (ref "R19")
      (value "470")
      (footprint "eagle-import:R0402")
      (fields (field (name "MFG") "Panasonic") (field (name "MPN") "ERJ-2GEJ471X"))
      (libsource (lib "eagle-import") (part "R-US_R0402"))
    )
    (comp (ref "R20")
      (value "0")
      (footprint "eagle-import:0402-RES")
      (description "Resistor, 1%, 0.125W")
      (fields
        (field (name "MANUFACTURER") "Panasonic")
        (field (name "MFG") "PANASONIC")
        (field (name "MPN") "DNI")
      )
      (libsource (lib "eagle-import") (part "RESISTOR0402-RES"))
    )
    (comp (ref "R21")
      (value "0")
      (footprint "eagle-import:0402-RES")
      (description "Resistor, 1%, 0.125W")
      (fields
        (field (name "MANUFACTURER") "Panasonic")
        (field (name "MFG") "PANASONIC")
        (field (name "MPN") "ERJ-2GE0R00X")
      )
      (libsource (lib "eagle-import") (part "RESISTOR0402-RES"))
    )
    (comp (ref "R22")
      (value "0")
      (footprint "eagle-import:0402-RES")
      (description "Resistor, 1%, 0.125W")
      (fields
        (field (name "MANUFACTURER") "Panasonic")
        (field (name "MFG") "PANASONIC")
        (field (name "MPN") "DNI")
      )
      (libsource (lib "eagle-import") (part "RESISTOR0402-RES"))
    )
    (comp (ref "R23")
      (value "0")
      (footprint "eagle-import:0402-RES")
      (description "Resistor, 1%, 0.125W")
      (fields
        (field (name "MANUFACTURER") "Panasonic")
        (field (name "MFG") "PANASONIC")
        (field (name "MPN") "ERJ-2GE0R00X")
      )
      (libsource (lib "eagle-import") (part "RESISTOR0402-RES"))
    )
    (comp (ref "R24")
      (value "10K")
      (footprint "eagle-import:0402-RES")
      (description "Resistor, 1%, 0.125W")
      (fields
        (field (name "MANUFACTURER") "Yaego")
        (field (name "MFG") "YAEGO")
        (field (name "MPN") "RC0402JR-0710KL")
      )
      (libsource (lib "eagle-import") (part "RESISTOR0402-RES"))
    )
    (comp (ref "R26")
      (value "75")
      (footprint "eagle-import:0402-RES")
      (description "Resistor, 1%, 0.125W")
      (fields
        (field (name "MANUFACTURER") "Panasonic")
        (field (name "MFG") "PANASONIC")
        (field (name "MPN") "ERJ-2GEJ750X")
      )
      (libsource (lib "eagle-import") (part "RESISTOR0402-RES"))
    )
    (comp (ref "R27")
      (value "0")
      (footprint "eagle-import:0402-RES")
      (description "Resistor, 1%, 0.125W")
      (fields
        (field (name "MANUFACTURER") "Panasonic")
        (field (name "MFG") "PANASONIC")
        (field (name "MPN") "DNI")
      )
      (libsource (lib "eagle-import") (part "RESISTOR0402-RES"))
    )
    (comp (ref "R28")
      (value "0")
      (footprint "eagle-import:0402-RES")
      (description "Resistor, 1%, 0.125W")
      (fields
        (field (name "MANUFACTURER") "Panasonic")
        (field (name "MFG") "PANASONIC")
        (field (name "MPN") "DNI")
      )
      (libsource (lib "eagle-import") (part "RESISTOR0402-RES"))
    )
    (comp (ref "R32")
      (value "0")
      (footprint "eagle-import:0402-RES")
      (description "Resistor, 1%, 0.125W")
      (fields
        (field (name "MANUFACTURER") "Panasonic")
        (field (name "MFG") "PANASONIC")
        (field (name "MPN") "ERJ-2GE0R00X")
      )
      (libsource (lib "eagle-import") (part "RESISTOR0402-RES"))
    )
    (comp (ref "R35")
      (value "10K")
      (footprint "eagle-import:0402-RES")
      (description "Resistor, 1%, 0.125W")
      (fields
        (field (name "MANUFACTURER") "Yaego")
        (field (name "MFG") "YAEGO")
        (field (name "MPN") "RC0402JR-0710KL")
      )
      (libsource (lib "eagle-import") (part "RESISTOR0402-RES"))
    )
    (comp (ref "R38")
      (value "1M")
      (footprint "eagle-import:0402-RES")
      (description "Resistor, 1%, 0.125W")
      (fields
        (field (name "MANUFACTURER") "Yaego")
        (field (name "MFG") "YAEGO")
        (field (name "MPN") "RC0402JR-071ML")
      )
      (libsource (lib "eagle-import") (part "RESISTOR0402-RES"))
    )
    (comp (ref "R39")
      (value "1M")
      (footprint "eagle-import:0402-RES")
      (description "Resistor, 1%, 0.125W")
      (fields
        (field (name "MANUFACTURER") "Yaego")
        (field (name "MFG") "YAEGO")
        (field (name "MPN") "RC0402JR-071ML")
      )
      (libsource (lib "eagle-import") (part "RESISTOR0402-RES"))
    )
    (comp (ref "R40")
      (value "10K")
      (footprint "eagle-import:0402-RES")
      (description "Resistor, 1%, 0.125W")
      (fields
        (field (name "MANUFACTURER") "Yaego")
        (field (name "MFG") "YAEGO")
        (field (name "MPN") "RC0402JR-0710KL")
      )
      (libsource (lib "eagle-import") (part "RESISTOR0402-RES"))
    )
    (comp (ref "R41")
      (value "75")
      (footprint "eagle-import:0402-RES")
      (description "Resistor, 1%, 0.125W")
      (fields
        (field (name "MANUFACTURER") "Panasonic")
        (field (name "MFG") "PANASONIC")
        (field (name "MPN") "DNI")
      )
      (libsource (lib "eagle-import") (part "RESISTOR0402-RES"))
    )
    (comp (ref "R42")
      (value "1M")
      (footprint "eagle-import:0402-RES")
      (description "Resistor, 1%, 0.125W")
      (fields
        (field (name "MANUFACTURER") "Yaego")
        (field (name "MFG") "YAEGO")
        (field (name "MPN") "RC0402JR-071ML")
      )
      (libsource (lib "eagle-import") (part "RESISTOR0402-RES"))
    )
    (comp (ref "R45")
      (value "1k")
      (footprint "eagle-import:0402-RES")
      (description "Resistor, 5%, 0.1W")
      (fields
        (field (name "MFG") "YAEGO")
        (field (name "MPN") "RC0402JR-071KL")
        (field (name "POWER") "0.1W")
        (field (name "TOLERANCE") "5%")
      )
      (libsource (lib "eagle-import") (part "RESISTOR"))
    )
    (comp (ref "R46")
      (value "0")
      (footprint "eagle-import:0402-RES")
      (description "Resistor, 1%, 0.125W")
      (fields
        (field (name "MANUFACTURER") "Panasonic")
        (field (name "MFG") "PANASONIC")
        (field (name "MPN") "ERJ-2GE0R00X")
      )
      (libsource (lib "eagle-import") (part "RESISTOR0402-RES"))
    )
    (comp (ref "R47")
      (value "10K")
      (footprint "eagle-import:0402-RES")
      (description "Resistor, 1%, 0.125W")
      (fields
        (field (name "MANUFACTURER") "Yaego")
        (field (name "MFG") "YAEGO")
        (field (name "MPN") "RC0402JR-0710KL")
      )
      (libsource (lib "eagle-import") (part "RESISTOR0402-RES"))
    )
    (comp (ref "R48")
      (value "0")
      (footprint "eagle-import:0402-RES")
      (description "Resistor, 1%, 0.125W")
      (fields
        (field (name "MANUFACTURER") "Panasonic")
        (field (name "MFG") "PANASONIC")
        (field (name "MPN") "ERJ-2GE0R00X")
      )
      (libsource (lib "eagle-import") (part "RESISTOR0402-RES"))
    )
    (comp (ref "R49")
      (value "0")
      (footprint "eagle-import:0402-RES")
      (description "Resistor, 1%, 0.125W")
      (fields
        (field (name "MANUFACTURER") "Panasonic")
        (field (name "MFG") "PANASONIC")
        (field (name "MPN") "ERJ-2GE0R00X")
      )
      (libsource (lib "eagle-import") (part "RESISTOR0402-RES"))
    )
    (comp (ref "R51")
      (value "100K")
      (footprint "eagle-import:R0402")
      (fields (field (name "MFG") "Panasonic") (field (name "MPN") "ERJ-2GEJ104X"))
      (libsource (lib "eagle-import") (part "R-US_R0402"))
    )
    (comp (ref "R54")
      (value "0")
      (footprint "eagle-import:0402-RES")
      (description "Resistor, 1%, 0.125W")
      (fields
        (field (name "MANUFACTURER") "Panasonic")
        (field (name "MFG") "PANASONIC")
        (field (name "MPN") "ERJ-2GE0R00X")
      )
      (libsource (lib "eagle-import") (part "RESISTOR0402-RES"))
    )
    (comp (ref "R55")
      (value "0")
      (footprint "eagle-import:0402-RES")
      (description "Resistor, 1%, 0.125W")
      (fields
        (field (name "MANUFACTURER") "Panasonic")
        (field (name "MFG") "PANASONIC")
        (field (name "MPN") "ERJ-2GE0R00X")
      )
      (libsource (lib "eagle-import") (part "RESISTOR0402-RES"))
    )
    (comp (ref "R56")
      (value "0")
      (footprint "eagle-import:0402-RES")
      (description "Resistor, 1%, 0.125W")
      (fields
        (field (name "MANUFACTURER") "Panasonic")
        (field (name "MFG") "PANASONIC")
        (field (name "MPN") "ERJ-2GE0R00X")
      )
      (libsource (lib "eagle-import") (part "RESISTOR0402-RES"))
    )
    (comp (ref "R57")
      (value "0")
      (footprint "eagle-import:0402-RES")
      (description "Resistor, 1%, 0.125W")
      (fields
        (field (name "MANUFACTURER") "Panasonic")
        (field (name "MFG") "PANASONIC")
        (field (name "MPN") "ERJ-2GE0R00X")
      )
      (libsource (lib "eagle-import") (part "RESISTOR0402-RES"))
    )
    (comp (ref "R58")
      (value "0")
      (footprint "eagle-import:0402-RES")
      (description "Resistor, 1%, 0.125W")
      (fields
        (field (name "MANUFACTURER") "Panasonic")
        (field (name "MFG") "PANASONIC")
        (field (name "MPN") "ERJ-2GE0R00X")
      )
      (libsource (lib "eagle-import") (part "RESISTOR0402-RES"))
    )
    (comp (ref "R59")
      (value "0")
      (footprint "eagle-import:0402-RES")
      (description "Resistor, 1%, 0.125W")
      (fields
        (field (name "MANUFACTURER") "Panasonic")
        (field (name "MFG") "PANASONIC")
        (field (name "MPN") "ERJ-2GE0R00X")
      )
      (libsource (lib "eagle-import") (part "RESISTOR0402-RES"))
    )
    (comp (ref "R60")
      (value "0")
      (footprint "eagle-import:0402-RES")
      (description "Resistor, 1%, 0.125W")
      (fields
        (field (name "MANUFACTURER") "Panasonic")
        (field (name "MFG") "PANASONIC")
        (field (name "MPN") "ERJ-2GE0R00X")
      )
      (libsource (lib "eagle-import") (part "RESISTOR0402-RES"))
    )
    (comp (ref "R61")
      (value "0")
      (footprint "eagle-import:0402-RES")
      (description "Resistor, 1%, 0.125W")
      (fields
        (field (name "MANUFACTURER") "Panasonic")
        (field (name "MFG") "PANASONIC")
        (field (name "MPN") "ERJ-2GE0R00X")
      )
      (libsource (lib "eagle-import") (part "RESISTOR0402-RES"))
    )
    (comp (ref "R62")
      (value "0")
      (footprint "eagle-import:0402-RES")
      (description "Resistor, 1%, 0.125W")
      (fields
        (field (name "MANUFACTURER") "Panasonic")
        (field (name "MFG") "PANASONIC")
        (field (name "MPN") "ERJ-2GE0R00X")
      )
      (libsource (lib "eagle-import") (part "RESISTOR0402-RES"))
    )
    (comp (ref "R63")
      (value "0")
      (footprint "eagle-import:0402-RES")
      (description "Resistor, 1%, 0.125W")
      (fields
        (field (name "MANUFACTURER") "Panasonic")
        (field (name "MFG") "PANASONIC")
        (field (name "MPN") "ERJ-2GE0R00X")
      )
      (libsource (lib "eagle-import") (part "RESISTOR0402-RES"))
    )
    (comp (ref "R64")
      (value "0")
      (footprint "eagle-import:0402-RES")
      (description "Resistor, 1%, 0.125W")
      (fields
        (field (name "MANUFACTURER") "Panasonic")
        (field (name "MFG") "PANASONIC")
        (field (name "MPN") "ERJ-2GE0R00X")
      )
      (libsource (lib "eagle-import") (part "RESISTOR0402-RES"))
    )
    (comp (ref "R65")
      (value "75")
      (footprint "eagle-import:0402-RES")
      (description "Resistor, 1%, 0.125W")
      (fields
        (field (name "MANUFACTURER") "Panasonic")
        (field (name "MFG") "PANASONIC")
        (field (name "MPN") "ERJ-2GEJ750X")
      )
      (libsource (lib "eagle-import") (part "RESISTOR0402-RES"))
    )
    (comp (ref "R66")
      (value "0")
      (footprint "eagle-import:0402-RES")
      (description "Resistor, 1%, 0.125W")
      (fields
        (field (name "MANUFACTURER") "Panasonic")
        (field (name "MFG") "PANASONIC")
        (field (name "MPN") "ERJ-2GE0R00X")
      )
      (libsource (lib "eagle-import") (part "RESISTOR0402-RES"))
    )
    (comp (ref "R67")
      (value "0")
      (footprint "eagle-import:0402-RES")
      (description "Resistor, 1%, 0.125W")
      (fields
        (field (name "MANUFACTURER") "Panasonic")
        (field (name "MFG") "PANASONIC")
        (field (name "MPN") "ERJ-2GE0R00X")
      )
      (libsource (lib "eagle-import") (part "RESISTOR0402-RES"))
    )
    (comp (ref "R69")
      (value "0")
      (footprint "eagle-import:0402-RES")
      (description "Resistor, 1%, 0.125W")
      (fields
        (field (name "MANUFACTURER") "Panasonic")
        (field (name "MFG") "PANASONIC")
        (field (name "MPN") "ERJ-2GE0R00X")
      )
      (libsource (lib "eagle-import") (part "RESISTOR0402-RES"))
    )
    (comp (ref "R70")
      (value "0")
      (footprint "eagle-import:0402-RES")
      (description "Resistor, 1%, 0.125W")
      (fields
        (field (name "MANUFACTURER") "Panasonic")
        (field (name "MFG") "PANASONIC")
        (field (name "MPN") "DNI")
      )
      (libsource (lib "eagle-import") (part "RESISTOR0402-RES"))
    )
    (comp (ref "R71")
      (value "0")
      (footprint "eagle-import:0402-RES")
      (description "Resistor, 1%, 0.125W")
      (fields
        (field (name "MANUFACTURER") "Panasonic")
        (field (name "MFG") "PANASONIC")
        (field (name "MPN") "ERJ-2GE0R00X")
      )
      (libsource (lib "eagle-import") (part "RESISTOR0402-RES"))
    )
    (comp (ref "R2000")
      (value "470")
      (footprint "eagle-import:0402-RES")
      (description "Resistor, 1%, 0.125W")
      (fields
        (field (name "MANUFACTURER") "Yaego")
        (field (name "MFG") "YAEGO")
        (field (name "MPN") "RC0402JR-07470RL")
      )
      (libsource (lib "eagle-import") (part "RESISTOR0402-RES"))
    )
    (comp (ref "RN1")
      (value "22R")
      (footprint "eagle-import:CAY16")
      (fields
        (field (name "MFG") "BOURNES")
        (field (name "MPN") "CAY16-220J4LF")
        (field (name "PACKAGE") "CAY16")
        (field (name "PARTNUM") "CAY16-220J4LF")
      )
      (libsource (lib "eagle-import") (part "4R-NCAY16"))
    )
    (comp (ref "SIM1")
      (value "SIM_CARD_NANO")
      (footprint "eagle-import:SIM_CARD_NANO")
      (fields
        (field (name "MFG") "GLOBAL CONNECTOR TECHNOLOGY")
        (field (name "MPN") "SIM8100-6-0-15-01-A")
        (field (name "MPN_1") "SIM8050-6-0-14-01-A")
      )
      (libsource (lib "eagle-import") (part "SIM_CARD_NANO"))
    )
    (comp (ref "SW1")
      (value "SWITCH_PANASONIC_EVP-BB2A1B000")
      (footprint "eagle-import:SWITCH_PANASONIC_EVPBB")
      (fields (field (name "MFG") "PANASONIC") (field (name "MPN") "EVP-BB2A1B000"))
      (libsource (lib "eagle-import") (part "SWITCH_PANASONIC_EVP-BB2A1B000"))
    )
    (comp (ref "SW3")
      (value "SWITCH_PANASONIC_EVP-BB2A1B000")
      (footprint "eagle-import:SWITCH_PANASONIC_EVPBB")
      (fields (field (name "MFG") "PANASONIC") (field (name "MPN") "EVP-BB2A1B000"))
      (libsource (lib "eagle-import") (part "SWITCH_PANASONIC_EVP-BB2A1B000"))
    )
    (comp (ref "SW4")
      (value "SWITCH_PANASONIC_EVP-BB2A1B000")
      (footprint "eagle-import:SWITCH_PANASONIC_EVPBB")
      (fields (field (name "MFG") "PANASONIC") (field (name "MPN") "EVP-BB2A1B000"))
      (libsource (lib "eagle-import") (part "SWITCH_PANASONIC_EVP-BB2A1B000"))
    )
    (comp (ref "TP1")
      (value "TPTP08R")
      (footprint "eagle-import:TP08R")
      (libsource (lib "eagle-import") (part "TPTP08R"))
    )
    (comp (ref "TP2")
      (value "TPTP08R")
      (footprint "eagle-import:TP08R")
      (libsource (lib "eagle-import") (part "TPTP08R"))
    )
    (comp (ref "TP4")
      (value "TPTP08R")
      (footprint "eagle-import:TP08R")
      (libsource (lib "eagle-import") (part "TPTP08R"))
    )
    (comp (ref "TP5")
      (value "TPTP08R")
      (footprint "eagle-import:TP08R")
      (libsource (lib "eagle-import") (part "TPTP08R"))
    )
    (comp (ref "TP6")
      (value "TPTP08R")
      (footprint "eagle-import:TP08R")
      (libsource (lib "eagle-import") (part "TPTP08R"))
    )
    (comp (ref "TP7")
      (value "TPTP08R")
      (footprint "eagle-import:TP08R")
      (libsource (lib "eagle-import") (part "TPTP08R"))
    )
    (comp (ref "TP8")
      (value "TPTP08R")
      (footprint "eagle-import:TP08R")
      (libsource (lib "eagle-import") (part "TPTP08R"))
    )
    (comp (ref "TP13")
      (value "TPTP08R")
      (footprint "eagle-import:TP08R")
      (libsource (lib "eagle-import") (part "TPTP08R"))
    )
    (comp (ref "TP14")
      (value "TPTP08R")
      (footprint "eagle-import:TP08R")
      (libsource (lib "eagle-import") (part "TPTP08R"))
    )
    (comp (ref "TP17")
      (value "TPTP08R")
      (footprint "eagle-import:TP08R")
      (libsource (lib "eagle-import") (part "TPTP08R"))
    )
    (comp (ref "TP20")
      (value "TPTP08R")
      (footprint "eagle-import:TP08R")
      (libsource (lib "eagle-import") (part "TPTP08R"))
    )
    (comp (ref "TP21")
      (value "TPTP08R")
      (footprint "eagle-import:TP08R")
      (libsource (lib "eagle-import") (part "TPTP08R"))
    )
    (comp (ref "TP22")
      (value "TPTP08R")
      (footprint "eagle-import:TP08R")
      (libsource (lib "eagle-import") (part "TPTP08R"))
    )
    (comp (ref "TP23")
      (value "TPTP08R")
      (footprint "eagle-import:TP08R")
      (libsource (lib "eagle-import") (part "TPTP08R"))
    )
    (comp (ref "TP24")
      (value "TPTP08R")
      (footprint "eagle-import:TP08R")
      (libsource (lib "eagle-import") (part "TPTP08R"))
    )
    (comp (ref "TP27")
      (value "TPTP08R")
      (footprint "eagle-import:TP08R")
      (libsource (lib "eagle-import") (part "TPTP08R"))
    )
    (comp (ref "TP28")
      (value "TPTP08R")
      (footprint "eagle-import:TP08R")
      (libsource (lib "eagle-import") (part "TPTP08R"))
    )
    (comp (ref "TP30")
      (value "TPTP08R")
      (footprint "eagle-import:TP08R")
      (libsource (lib "eagle-import") (part "TPTP08R"))
    )
    (comp (ref "U$1")
      (value "TESTPAD")
      (footprint "eagle-import:TESTPAD")
      (libsource (lib "eagle-import") (part "TESTPAD"))
    )
    (comp (ref "U$2")
      (value "TESTPAD")
      (footprint "eagle-import:TESTPAD")
      (libsource (lib "eagle-import") (part "TESTPAD"))
    )
    (comp (ref "U1")
      (value "ST_MICRO_BAT_CHARGER_L6924U013")
      (footprint "eagle-import:BAT_CHARGE_ST_MICRO_L6924U")
      (fields (field (name "MFG") "ST Micro") (field (name "PARTNUM") "L6924UTR"))
      (libsource (lib "eagle-import") (part "ST_MICRO_BAT_CHARGER_L6924U013"))
    )
    (comp (ref "U2")
      (value "TPS63021")
      (footprint "eagle-import:QFN-14-POWERPAD3X4DSJ")
      (fields
        (field (name "MFG") "TI")
        (field (name "MPN") "TPS63021DSJ")
        (field (name "MPN_1") "TPS63021DSJR")
      )
      (libsource (lib "eagle-import") (part "TPS63021"))
    )
    (comp (ref "U3")
      (value "MICROCHIP_FLASH_MEM")
      (footprint "eagle-import:TDFN8_5X6")
      (fields (field (name "MFG") "MICROCHIP") (field (name "MPN") "SST26VF016BT-104I/MF"))
      (libsource (lib "eagle-import") (part "MICROCHIP_FLASH_MEM"))
    )
    (comp (ref "U4")
      (value "DIODE_DUAL_SCHOTKEY")
      (footprint "eagle-import:SOT23-3")
      (fields (field (name "MFG") "FAIRCHILD") (field (name "MPN") "BAT54C"))
      (libsource (lib "eagle-import") (part "DIODE_DUAL_SCHOTKEY"))
    )
    (comp (ref "U5")
      (value "MK20DX128VLH5")
      (footprint "eagle-import:MK20DX128VLH5")
      (fields (field (name "MFG") "Freescale") (field (name "MPN") "MK22FN1M0VLH12"))
      (libsource (lib "eagle-import") (part "MK20DX128VLH5"))
    )
    (comp (ref "U6")
      (value "FREESCALE_MKL17Z256VFM4")
      (footprint "eagle-import:QFN_32_5X5")
      (fields (field (name "MFG") "FREESCALE") (field (name "MPN") "MKL17Z256VFM4"))
      (libsource (lib "eagle-import") (part "FREESCALE_MKL17Z256VFM4"))
    )
    (comp (ref "U7")
      (value "PESD12VL2BT,215")
      (footprint "eagle-import:SOT23")
      (fields (field (name "MFG") "NXP"))
      (libsource (lib "eagle-import") (part "PESD12VL2BT,215"))
    )
    (comp (ref "U8")
      (value "VOLTAGE_TRANSLATOR_4_BIT")
      (footprint "eagle-import:UQFN_16")
      (fields (field (name "MFG") "TI") (field (name "MPN") "SN74AVC4T774RSVR"))
      (libsource (lib "eagle-import") (part "VOLTAGE_TRANSLATOR_4_BIT"))
    )
    (comp (ref "U9")
      (value "PESD12VL2BT,215")
      (footprint "eagle-import:SOT23")
      (fields (field (name "MFG") "NXP"))
      (libsource (lib "eagle-import") (part "PESD12VL2BT,215"))
    )
    (comp (ref "U19")
      (value "MAX1704X")
      (footprint "eagle-import:TDFN-8")
      (description "Battery Fuel Gauge")
      (fields (field (name "MFG") "Maxim") (field (name "MPN") "MAX17043G+U"))
      (libsource (lib "eagle-import") (part "MAX1704X"))
    )
    (comp (ref "U420")
      (value "SARA-U2XX")
      (footprint "eagle-import:91-PIN_LGA")
      (fields
        (field (name "MFG") "U-BLOX")
        (field (name "PARTNUMBER") "SARA-U270")
        (field (name "MPN") "SARA-U260-00S")
        (field (name "PARTNUMBER_1") "SARA-U260")
      )
      (libsource (lib "eagle-import") (part "SARA-U2XX"))
    )
    (comp (ref "X1")
      (value "16 MHz")
      (footprint "eagle-import:CRYSTAL_RESONATOR_MURATA_CSTCE")
      (fields (field (name "MFG") "MURATA") (field (name "MPN") "CSTCE16M0V53-R0"))
      (libsource (lib "eagle-import") (part "CERAMIC_RESONATOR_16MHZ_MURATA_CSTCE"))
    )
    (comp (ref "X2")
      (value "32.768 kHz")
      (footprint "eagle-import:CRYSTAL_ST3215SB")
      (fields (field (name "MFG") "AVX/ELCO/KYOCERA") (field (name "MPN") "ST3215SB32768E0HPWBB"))
      (libsource (lib "eagle-import") (part "CRYSTAL_32.768K_AVX"))
    )
    (comp (ref "X3")
      (value "32.768 kHz")
      (footprint "eagle-import:CRYSTAL_ST3215SB")
      (fields (field (name "MFG") "AVX/ELCO/KYOCERA") (field (name "MPN") "ST3215SB32768E0HPWBB"))
      (libsource (lib "eagle-import") (part "CRYSTAL_32.768K_AVX"))
    )
  )
  (nets
    (net (code "1") (name "/+3.3V") (class "Default")
      (node (ref "C35") (pin "1") (pinfunction "1_1") (pintype "passive"))
      (node (ref "C36") (pin "1") (pinfunction "1_1") (pintype "passive"))
      (node (ref "C37") (pin "1") (pinfunction "1_1") (pintype "passive"))
      (node (ref "C38") (pin "1") (pinfunction "1_1") (pintype "passive"))
      (node (ref "J9") (pin "1") (pinfunction "1_1") (pintype "bidirectional"))
      (node (ref "JRIGHT_B") (pin "1") (pinfunction "1_1") (pintype "passive"))
      (node (ref "R16") (pin "1") (pinfunction "1_1") (pintype "passive"))
      (node (ref "R17") (pin "1") (pinfunction "1_1") (pintype "passive"))
      (node (ref "R18") (pin "1") (pinfunction "1_1") (pintype "passive"))
      (node (ref "R2") (pin "2") (pinfunction "2_2") (pintype "passive"))
      (node (ref "R20") (pin "1") (pinfunction "1_1") (pintype "passive"))
      (node (ref "R21") (pin "1") (pinfunction "1_1") (pintype "passive"))
      (node (ref "R22") (pin "1") (pinfunction "1_1") (pintype "passive"))
      (node (ref "R24") (pin "2") (pinfunction "2_2") (pintype "passive"))
      (node (ref "R35") (pin "2") (pinfunction "2_2") (pintype "passive"))
      (node (ref "R4") (pin "1") (pinfunction "1_1") (pintype "passive"))
      (node (ref "R40") (pin "2") (pinfunction "2_2") (pintype "passive"))
      (node (ref "R42") (pin "2") (pinfunction "2_2") (pintype "passive"))
      (node (ref "R47") (pin "2") (pinfunction "2_2") (pintype "passive"))
      (node (ref "R48") (pin "1") (pinfunction "1_1") (pintype "passive"))
      (node (ref "R60") (pin "1") (pinfunction "1_1") (pintype "passive"))
      (node (ref "R67") (pin "2") (pinfunction "2_2") (pintype "passive"))
    )
    (net (code "2") (name "/+3.3V_GOOD") (class "Default")
      (node (ref "R42") (pin "1") (pinfunction "1_1") (pintype "passive"))
      (node (ref "U2") (pin "14") (pinfunction "PG_14") (pintype "bidirectional"))
      (node (ref "U5") (pin "39") (pinfunction "PTB16_39") (pintype "bidirectional"))
    )
    (net (code "3") (name "/AGND") (class "Default")
      (node (ref "C13") (pin "2") (pinfunction "2_2") (pintype "passive"))
      (node (ref "C14") (pin "2") (pinfunction "2_2") (pintype "passive"))
      (node (ref "C15") (pin "2") (pinfunction "2_2") (pintype "passive"))
      (node (ref "L3") (pin "1") (pinfunction "P$1_1") (pintype "bidirectional"))
      (node (ref "U5") (pin "15") (pinfunction "VREFL_15") (pintype "bidirectional"))
      (node (ref "U5") (pin "16") (pinfunction "VSSA_16") (pintype "bidirectional"))
    )
    (net (code "4") (name "/ANT_DET$62") (class "Default")
      (node (ref "U420") (pin "62") (pinfunction "ANT_DET$62_62") (pintype "power_in"))
    )
    (net (code "5") (name "/AREF") (class "Default")
      (node (ref "C14") (pin "1") (pinfunction "1_1") (pintype "passive"))
      (node (ref "R19") (pin "2") (pinfunction "2_2") (pintype "passive"))
      (node (ref "R23") (pin "2") (pinfunction "2_2") (pintype "passive"))
      (node (ref "U5") (pin "14") (pinfunction "VREFH_14") (pintype "bidirectional"))
    )
    (net (code "6") (name "/BL_SCL") (class "Default")
      (node (ref "R40") (pin "1") (pinfunction "1_1") (pintype "passive"))
      (node (ref "R58") (pin "2") (pinfunction "2_2") (pintype "passive"))
      (node (ref "U19") (pin "7") (pinfunction "SCL_7") (pintype "bidirectional"))
      (node (ref "U5") (pin "37") (pinfunction "PTB2_37") (pintype "bidirectional"))
    )
    (net (code "7") (name "/BL_SDA") (class "Default")
      (node (ref "R35") (pin "1") (pinfunction "1_1") (pintype "passive"))
      (node (ref "R59") (pin "2") (pinfunction "2_2") (pintype "passive"))
      (node (ref "U19") (pin "8") (pinfunction "SDA_8") (pintype "bidirectional"))
      (node (ref "U5") (pin "38") (pinfunction "PTB3_38") (pintype "bidirectional"))
    )
    (net (code "8") (name "/EZP_CS") (class "Default")
      (node (ref "R55") (pin "2") (pinfunction "2_2") (pintype "passive"))
      (node (ref "U5") (pin "26") (pinfunction "PTA4_26") (pintype "bidirectional"))
    )
    (net (code "9") (name "/I2S_TXD$35") (class "Default")
      (node (ref "U420") (pin "35") (pinfunction "I2S_TXD$35_35") (pintype "power_in"))
    )
    (net (code "10") (name "/I2S_WA$34") (class "Default")
      (node (ref "U420") (pin "34") (pinfunction "I2S_WA$34_34") (pintype "power_in"))
    )
    (net (code "11") (name "/M1_LED") (class "Default")
      (node (ref "D1") (pin "ANODE") (pinfunction "ANODE_ANODE") (pintype "bidirectional"))
      (node (ref "U5") (pin "42") (pinfunction "PTB19_42") (pintype "bidirectional"))
    )
    (net (code "12") (name "/M1_RESET") (class "Default")
      (node (ref "C24") (pin "1") (pinfunction "1_1") (pintype "passive"))
      (node (ref "C51") (pin "1") (pinfunction "1_1") (pintype "passive"))
      (node (ref "L6") (pin "2") (pinfunction "P$2_2") (pintype "bidirectional"))
      (node (ref "R47") (pin "1") (pinfunction "1_1") (pintype "passive"))
      (node (ref "SW1") (pin "A") (pinfunction "P$1_A") (pintype "bidirectional"))
      (node (ref "SW1") (pin "A2") (pinfunction "P$1_A2") (pintype "bidirectional"))
      (node (ref "TP17") (pin "TP") (pinfunction "TP_TP") (pintype "input"))
      (node (ref "U5") (pin "34") (pinfunction "RESET_B_34") (pintype "bidirectional"))
      (node (ref "U6") (pin "26") (pinfunction "PTC5_26") (pintype "bidirectional"))
    )
    (net (code "13") (name "/M1_TCK_SWDCLK") (class "Default")
      (node (ref "R54") (pin "2") (pinfunction "2_2") (pintype "passive"))
      (node (ref "TP4") (pin "TP") (pinfunction "TP_TP") (pintype "input"))
      (node (ref "U5") (pin "22") (pinfunction "PTA0_22") (pintype "bidirectional"))
    )
    (net (code "14") (name "/M1_TDI") (class "Default")
      (node (ref "R57") (pin "2") (pinfunction "2_2") (pintype "passive"))
      (node (ref "R66") (pin "2") (pinfunction "2_2") (pintype "passive"))
      (node (ref "TP6") (pin "TP") (pinfunction "TP_TP") (pintype "input"))
      (node (ref "U5") (pin "23") (pinfunction "PTA1_23") (pintype "bidirectional"))
    )
    (net (code "15") (name "/M1_TDO_SWO") (class "Default")
      (node (ref "R56") (pin "2") (pinfunction "2_2") (pintype "passive"))
      (node (ref "TP7") (pin "TP") (pinfunction "TP_TP") (pintype "input"))
      (node (ref "U5") (pin "24") (pinfunction "PTA2_24") (pintype "bidirectional"))
    )
    (net (code "16") (name "/M1_TMS_SWDIO") (class "Default")
      (node (ref "R14") (pin "2") (pinfunction "2_2") (pintype "passive"))
      (node (ref "TP8") (pin "TP") (pinfunction "TP_TP") (pintype "input"))
      (node (ref "U5") (pin "25") (pinfunction "PTA3_25") (pintype "bidirectional"))
    )
    (net (code "17") (name "/M1_TX_TO_M2_RX") (class "Default")
      (node (ref "R61") (pin "1") (pinfunction "1_1") (pintype "passive"))
      (node (ref "U5") (pin "49") (pinfunction "PTC4_49") (pintype "bidirectional"))
    )
    (net (code "18") (name "/M2_MISO") (class "Default")
      (node (ref "U3") (pin "2") (pinfunction "SO_2") (pintype "bidirectional"))
      (node (ref "U6") (pin "1") (pinfunction "PTE0_1") (pintype "bidirectional"))
    )
    (net (code "19") (name "/M2_MOSI") (class "Default")
      (node (ref "U3") (pin "5") (pinfunction "SI_5") (pintype "bidirectional"))
      (node (ref "U6") (pin "2") (pinfunction "PTE1_2") (pintype "bidirectional"))
    )
    (net (code "20") (name "/M2_RESET") (class "Default")
      (node (ref "SW3") (pin "A") (pinfunction "P$1_A") (pintype "bidirectional"))
      (node (ref "SW3") (pin "A2") (pinfunction "P$1_A2") (pintype "bidirectional"))
      (node (ref "TP27") (pin "TP") (pinfunction "TP_TP") (pintype "input"))
      (node (ref "U5") (pin "41") (pinfunction "PTB18_41") (pintype "bidirectional"))
      (node (ref "U6") (pin "19") (pinfunction "RESET_B_PTA20_19") (pintype "bidirectional"))
    )
    (net (code "21") (name "/M2_SCK") (class "Default")
      (node (ref "U3") (pin "6") (pinfunction "SCK_6") (pintype "bidirectional"))
      (node (ref "U6") (pin "30") (pinfunction "PTD5_30") (pintype "bidirectional"))
    )
    (net (code "22") (name "/M2_SS") (class "Default")
      (node (ref "U3") (pin "1") (pinfunction "~{CE}_1") (pintype "bidirectional"))
      (node (ref "U6") (pin "29") (pinfunction "PTD4_29") (pintype "bidirectional"))
    )
    (net (code "23") (name "/M2_TCK_SWDCLK") (class "Default")
      (node (ref "TP14") (pin "TP") (pinfunction "TP_TP") (pintype "input"))
      (node (ref "U6") (pin "10") (pinfunction "PTA0_10") (pintype "bidirectional"))
    )
    (net (code "24") (name "/M2_TMS_SWDIO") (class "Default")
      (node (ref "TP2") (pin "TP") (pinfunction "TP_TP") (pintype "input"))
      (node (ref "U6") (pin "13") (pinfunction "PTA3_13") (pintype "bidirectional"))
    )
    (net (code "25") (name "/M2_TX_TO_M1_RX") (class "Default")
      (node (ref "R62") (pin "1") (pinfunction "1_1") (pintype "passive"))
      (node (ref "U5") (pin "46") (pinfunction "PTC3_46") (pintype "bidirectional"))
    )
    (net (code "26") (name "/M2_UBLOX_RX") (class "Default")
      (node (ref "R63") (pin "1") (pinfunction "1_1") (pintype "passive"))
      (node (ref "TP24") (pin "TP") (pinfunction "TP_TP") (pintype "input"))
      (node (ref "U8") (pin "P$2") (pinfunction "A2_P$2") (pintype "bidirectional"))
    )
    (net (code "27") (name "/M2_UBLOX_TX") (class "Default")
      (node (ref "R64") (pin "1") (pinfunction "1_1") (pintype "passive"))
      (node (ref "TP23") (pin "TP") (pinfunction "TP_TP") (pintype "input"))
      (node (ref "U8") (pin "P$1") (pinfunction "A1_P$1") (pintype "bidirectional"))
    )
    (net (code "28") (name "/RSVD$31") (class "Default")
      (node (ref "U420") (pin "31") (pinfunction "RSVD$31_31") (pintype "power_in"))
    )
    (net (code "29") (name "/SCL$27") (class "Default")
      (node (ref "U420") (pin "27") (pinfunction "SCL$27_27") (pintype "power_in"))
    )
    (net (code "30") (name "/SDA$26") (class "Default")
      (node (ref "U420") (pin "26") (pinfunction "SDA$26_26") (pintype "power_in"))
    )
    (net (code "31") (name "/UBLOX_1.8V_SUPPLY") (class "Default")
      (node (ref "R49") (pin "1") (pinfunction "1_1") (pintype "passive"))
      (node (ref "U420") (pin "4") (pinfunction "V_INT$4_4") (pintype "bidirectional"))
    )
    (net (code "32") (name "/UBLOX_ANT") (class "Default")
      (node (ref "ANT_UFL") (pin "SIGNAL") (pinfunction "SIGNAL_SIGNAL") (pintype "bidirectional"))
      (node (ref "U420") (pin "56") (pinfunction "ANT$56_56") (pintype "power_in"))
    )
    (net (code "33") (name "/UBLOX_ANT_IND") (class "Default")
      (node (ref "U420") (pin "16") (pinfunction "GPIO1$16_16") (pintype "bidirectional"))
    )
    (net (code "34") (name "/UBLOX_PWR_IN") (class "Default")
      (node (ref "C39") (pin "2") (pinfunction "2_2") (pintype "passive"))
      (node (ref "C40") (pin "2") (pinfunction "2_2") (pintype "passive"))
      (node (ref "C46") (pin "2") (pinfunction "2_2") (pintype "passive"))
      (node (ref "C47") (pin "1") (pinfunction "1_1") (pintype "passive"))
      (node (ref "C6") (pin "2") (pinfunction "2_2") (pintype "passive"))
      (node (ref "D3") (pin "ANODE") (pinfunction "ANODE_ANODE") (pintype "bidirectional"))
      (node (ref "J9") (pin "2") (pinfunction "2_2") (pintype "bidirectional"))
      (node (ref "J9") (pin "4") (pinfunction "4_4") (pintype "bidirectional"))
      (node (ref "L7") (pin "1") (pinfunction "P$1_1") (pintype "bidirectional"))
      (node (ref "R22") (pin "2") (pinfunction "2_2") (pintype "passive"))
      (node (ref "R27") (pin "2") (pinfunction "2_2") (pintype "passive"))
      (node (ref "TP28") (pin "TP") (pinfunction "TP_TP") (pintype "input"))
    )
    (net (code "35") (name "/UBLOX_PWR_ON") (class "Default")
      (node (ref "R51") (pin "2") (pinfunction "2_2") (pintype "passive"))
      (node (ref "U420") (pin "15") (pinfunction "PWR_ON$15_15") (pintype "bidirectional"))
      (node (ref "U6") (pin "11") (pinfunction "PTA1_11") (pintype "bidirectional"))
    )
    (net (code "36") (name "/UBLOX_RESET_N") (class "Default")
      (node (ref "C43") (pin "1") (pinfunction "1_1") (pintype "passive"))
      (node (ref "L6") (pin "1") (pinfunction "P$1_1") (pintype "bidirectional"))
      (node (ref "U420") (pin "18") (pinfunction "RESET_N$18_18") (pintype "bidirectional"))
    )
    (net (code "37") (name "/UBLOX_RXD") (class "Default")
      (node (ref "TP22") (pin "TP") (pinfunction "TP_TP") (pintype "input"))
      (node (ref "U420") (pin "13") (pinfunction "RXD$13_13") (pintype "bidirectional"))
      (node (ref "U8") (pin "P$11") (pinfunction "B2_P$11") (pintype "bidirectional"))
    )
    (net (code "38") (name "/UBLOX_SARA_USB_D_N") (class "Default")
      (node (ref "U$2") (pin "P$1") (pinfunction "P$1_P$1") (pintype "bidirectional"))
      (node (ref "U420") (pin "28") (pinfunction "USB_D-$28_28") (pintype "power_in"))
    )
    (net (code "39") (name "/UBLOX_SARA_USB_D_P") (class "Default")
      (node (ref "U$1") (pin "P$1") (pinfunction "P$1_P$1") (pintype "bidirectional"))
      (node (ref "U420") (pin "29") (pinfunction "USB_D+$29_29") (pintype "power_in"))
    )
    (net (code "40") (name "/UBLOX_SIM_CLK") (class "Default")
      (node (ref "C42") (pin "1") (pinfunction "1_1") (pintype "passive"))
      (node (ref "SIM1") (pin "C3") (pinfunction "CLK_C3") (pintype "bidirectional"))
      (node (ref "U420") (pin "38") (pinfunction "SIM_CLK$38_38") (pintype "power_in"))
    )
    (net (code "41") (name "/UBLOX_SIM_IO") (class "Default")
      (node (ref "C44") (pin "1") (pinfunction "1_1") (pintype "passive"))
      (node (ref "SIM1") (pin "C7") (pinfunction "IO_C7") (pintype "bidirectional"))
      (node (ref "U420") (pin "39") (pinfunction "SIM_IO$39_39") (pintype "power_in"))
    )
    (net (code "42") (name "/UBLOX_SIM_RST") (class "Default")
      (node (ref "C41") (pin "1") (pinfunction "1_1") (pintype "passive"))
      (node (ref "SIM1") (pin "C2") (pinfunction "RST_C2") (pintype "bidirectional"))
      (node (ref "U420") (pin "40") (pinfunction "SIM_RST$40_40") (pintype "power_in"))
    )
    (net (code "43") (name "/UBLOX_SIM_VSIM") (class "Default")
      (node (ref "C2") (pin "1") (pinfunction "1_1") (pintype "passive"))
      (node (ref "C45") (pin "1") (pinfunction "1_1") (pintype "passive"))
      (node (ref "SIM1") (pin "C1") (pinfunction "VCC_C1") (pintype "bidirectional"))
      (node (ref "SIM1") (pin "C6") (pinfunction "VCC2_C6") (pintype "bidirectional"))
      (node (ref "U420") (pin "41") (pinfunction "VSIM$41_41") (pintype "bidirectional"))
    )
    (net (code "44") (name "/UBLOX_TXD") (class "Default")
      (node (ref "TP21") (pin "TP") (pinfunction "TP_TP") (pintype "input"))
      (node (ref "U420") (pin "12") (pinfunction "TXD$12_12") (pintype "power_in"))
      (node (ref "U8") (pin "P$12") (pinfunction "B1_P$12") (pintype "bidirectional"))
    )
    (net (code "45") (name "/UBLOX_USB_DET") (class "Default")
      (node (ref "R32") (pin "1") (pinfunction "1_1") (pintype "passive"))
      (node (ref "U420") (pin "17") (pinfunction "V_USB_DET$17_17") (pintype "bidirectional"))
    )
    (net (code "46") (name "/UBLOX_VCC") (class "Default")
      (node (ref "L7") (pin "2") (pinfunction "P$2_2") (pintype "bidirectional"))
      (node (ref "TP30") (pin "TP") (pinfunction "TP_TP") (pintype "input"))
      (node (ref "U420") (pin "51") (pinfunction "VCC$51_51") (pintype "bidirectional"))
      (node (ref "U420") (pin "52") (pinfunction "VCC$52_52") (pintype "bidirectional"))
      (node (ref "U420") (pin "53") (pinfunction "VCC$53_53") (pintype "bidirectional"))
    )
    (net (code "47") (name "/UBLOX_V_BCKP") (class "Default")
      (node (ref "R51") (pin "1") (pinfunction "1_1") (pintype "passive"))
      (node (ref "U420") (pin "2") (pinfunction "V_BCKP$2_2") (pintype "bidirectional"))
    )
    (net (code "48") (name "/UBLOX_WAKE_M2") (class "Default")
      (node (ref "R12") (pin "2") (pinfunction "2_2") (pintype "passive"))
      (node (ref "U420") (pin "23") (pinfunction "GPIO2$23_23") (pintype "power_in"))
    )
    (net (code "49") (name "/USB_5V") (class "Default")
      (node (ref "F6") (pin "1") (pinfunction "P$1_1") (pintype "bidirectional"))
      (node (ref "J1") (pin "VCC") (pinfunction "VBUS_VCC") (pintype "bidirectional"))
      (node (ref "JLEFT_A") (pin "6") (pinfunction "6_6") (pintype "passive"))
      (node (ref "TP1") (pin "TP") (pinfunction "TP_TP") (pintype "input"))
    )
    (net (code "50") (name "/USB_D_N") (class "Default")
      (node (ref "RN1") (pin "7") (pinfunction "2_7") (pintype "passive"))
      (node (ref "U5") (pin "6") (pinfunction "USB0_DM_6") (pintype "bidirectional"))
      (node (ref "U9") (pin "1") (pinfunction "P$1_1") (pintype "bidirectional"))
    )
    (net (code "51") (name "/USB_D_P") (class "Default")
      (node (ref "RN1") (pin "6") (pinfunction "2_6") (pintype "passive"))
      (node (ref "U5") (pin "5") (pinfunction "USB0_DP_5") (pintype "bidirectional"))
      (node (ref "U9") (pin "2") (pinfunction "P$2_2") (pintype "bidirectional"))
    )
    (net (code "52") (name "/USB_ID") (class "Default")
      (node (ref "J1") (pin "ID") (pinfunction "ID_ID") (pintype "bidirectional"))
      (node (ref "R66") (pin "1") (pinfunction "1_1") (pintype "passive"))
      (node (ref "U7") (pin "2") (pinfunction "P$2_2") (pintype "bidirectional"))
    )
    (net (code "53") (name "/USB_IN") (class "Default")
      (node (ref "C1") (pin "1") (pinfunction "1_1") (pintype "passive"))
      (node (ref "C11") (pin "1") (pinfunction "1_1") (pintype "passive"))
      (node (ref "C12") (pin "1") (pinfunction "1_1") (pintype "passive"))
      (node (ref "F6") (pin "2") (pinfunction "P$2_2") (pintype "bidirectional"))
      (node (ref "J2") (pin "2") (pinfunction "2_2") (pintype "bidirectional"))
      (node (ref "J2") (pin "4") (pinfunction "4_4") (pintype "bidirectional"))
      (node (ref "R13") (pin "1") (pinfunction "1_1") (pintype "passive"))
      (node (ref "R6") (pin "1") (pinfunction "1_1") (pintype "passive"))
      (node (ref "TP5") (pin "TP") (pinfunction "TP_TP") (pintype "input"))
      (node (ref "U7") (pin "1") (pinfunction "P$1_1") (pintype "bidirectional"))
    )
    (net (code "54") (name "/USB_IN_D_N") (class "Default")
      (node (ref "J1") (pin "D-") (pinfunction "D-_D-") (pintype "bidirectional"))
      (node (ref "RN1") (pin "2") (pinfunction "1_2") (pintype "passive"))
    )
    (net (code "55") (name "/USB_IN_D_P") (class "Default")
      (node (ref "J1") (pin "D+") (pinfunction "D+_D+") (pintype "bidirectional"))
      (node (ref "RN1") (pin "3") (pinfunction "1_3") (pintype "passive"))
    )
    (net (code "56") (name "/USER01") (class "Default")
      (node (ref "JLEFT_B") (pin "1") (pinfunction "1_1") (pintype "passive"))
      (node (ref "U5") (pin "29") (pinfunction "PTA13_29") (pintype "bidirectional"))
    )
    (net (code "57") (name "/USER02") (class "Default")
      (node (ref "JLEFT_B") (pin "2") (pinfunction "2_2") (pintype "passive"))
      (node (ref "U5") (pin "28") (pinfunction "PTA12_28") (pintype "bidirectional"))
    )
    (net (code "58") (name "/USER03") (class "Default")
      (node (ref "JLEFT_B") (pin "3") (pinfunction "3_3") (pintype "passive"))
      (node (ref "U5") (pin "27") (pinfunction "PTA5_27") (pintype "bidirectional"))
    )
    (net (code "59") (name "/USER04") (class "Default")
      (node (ref "JLEFT_A") (pin "4") (pinfunction "4_4") (pintype "passive"))
      (node (ref "U5") (pin "1") (pinfunction "PTE0_1") (pintype "bidirectional"))
    )
    (net (code "60") (name "/USER05") (class "Default")
      (node (ref "JLEFT_A") (pin "3") (pinfunction "3_3") (pintype "passive"))
      (node (ref "U5") (pin "2") (pinfunction "PTE1_2") (pintype "bidirectional"))
    )
    (net (code "61") (name "/USER06") (class "Default")
      (node (ref "JLEFT_C") (pin "6") (pinfunction "6_6") (pintype "passive"))
      (node (ref "U5") (pin "35") (pinfunction "PTB0_35") (pintype "bidirectional"))
    )
    (net (code "62") (name "/USER07") (class "Default")
      (node (ref "JLEFT_B") (pin "4") (pinfunction "4_4") (pintype "passive"))
      (node (ref "U5") (pin "36") (pinfunction "PTB1_36") (pintype "bidirectional"))
    )
    (net (code "63") (name "/USER08") (class "Default")
      (node (ref "JLEFT_C") (pin "5") (pinfunction "5_5") (pintype "passive"))
      (node (ref "U5") (pin "18") (pinfunction "DAC0_OUT_18") (pintype "bidirectional"))
    )
    (net (code "64") (name "/USER09") (class "Default")
      (node (ref "JRIGHT_B") (pin "5") (pinfunction "5_5") (pintype "passive"))
      (node (ref "U5") (pin "45") (pinfunction "PTC2_45") (pintype "bidirectional"))
    )
    (net (code "65") (name "/USER10") (class "Default")
      (node (ref "JRIGHT_B") (pin "6") (pinfunction "6_6") (pintype "passive"))
      (node (ref "U5") (pin "44") (pinfunction "PTC1_44") (pintype "bidirectional"))
    )
    (net (code "66") (name "/USER11") (class "Default")
      (node (ref "JRIGHT_B") (pin "4") (pinfunction "4_4") (pintype "passive"))
      (node (ref "U5") (pin "43") (pinfunction "PTC0_43") (pintype "bidirectional"))
    )
    (net (code "67") (name "/USER12") (class "Default")
      (node (ref "JRIGHT_A") (pin "1") (pinfunction "1_1") (pintype "passive"))
      (node (ref "U5") (pin "53") (pinfunction "PTC8_53") (pintype "bidirectional"))
    )
    (net (code "68") (name "/USER13") (class "Default")
      (node (ref "JLEFT_A") (pin "2") (pinfunction "2_2") (pintype "passive"))
      (node (ref "U5") (pin "58") (pinfunction "PTD1_58") (pintype "bidirectional"))
    )
    (net (code "69") (name "/USER14") (class "Default")
      (node (ref "JLEFT_A") (pin "1") (pinfunction "1_1") (pintype "passive"))
      (node (ref "U5") (pin "59") (pinfunction "PTD2_59") (pintype "bidirectional"))
    )
    (net (code "70") (name "/USER15") (class "Default")
      (node (ref "JLEFT_B") (pin "5") (pinfunction "5_5") (pintype "passive"))
      (node (ref "U5") (pin "60") (pinfunction "PTD3_60") (pintype "bidirectional"))
    )
    (net (code "71") (name "/USER16") (class "Default")
      (node (ref "JRIGHT_A") (pin "3") (pinfunction "3_3") (pintype "passive"))
      (node (ref "U5") (pin "61") (pinfunction "PTD4_61") (pintype "bidirectional"))
    )
    (net (code "72") (name "/USER17") (class "Default")
      (node (ref "JLEFT_B") (pin "6") (pinfunction "6_6") (pintype "passive"))
      (node (ref "U5") (pin "62") (pinfunction "PTD5_62") (pintype "bidirectional"))
    )
    (net (code "73") (name "/USER18") (class "Default")
      (node (ref "JRIGHT_A") (pin "2") (pinfunction "2_2") (pintype "passive"))
      (node (ref "U5") (pin "63") (pinfunction "PTD6_63") (pintype "bidirectional"))
    )
    (net (code "74") (name "/USER19") (class "Default")
      (node (ref "JRIGHT_A") (pin "4") (pinfunction "4_4") (pintype "passive"))
      (node (ref "U5") (pin "64") (pinfunction "PTD7_64") (pintype "bidirectional"))
    )
    (net (code "75") (name "/USER20") (class "Default")
      (node (ref "JRIGHT_C") (pin "1") (pinfunction "1_1") (pintype "passive"))
      (node (ref "U5") (pin "9") (pinfunction "PGA0_DP_9") (pintype "bidirectional"))
    )
    (net (code "76") (name "/USER21") (class "Default")
      (node (ref "JLEFT_C") (pin "1") (pinfunction "1_1") (pintype "passive"))
      (node (ref "U5") (pin "12") (pinfunction "PGA1_DM_12") (pintype "bidirectional"))
    )
    (net (code "77") (name "/USER22") (class "Default")
      (node (ref "JRIGHT_B") (pin "3") (pinfunction "3_3") (pintype "passive"))
      (node (ref "R1") (pin "2") (pinfunction "2_2") (pintype "passive"))
    )
    (net (code "78") (name "/USER23") (class "Default")
      (node (ref "JRIGHT_C") (pin "6") (pinfunction "6_6") (pintype "passive"))
      (node (ref "U5") (pin "51") (pinfunction "PTC6_51") (pintype "bidirectional"))
    )
    (net (code "79") (name "/USER24") (class "Default")
      (node (ref "JRIGHT_C") (pin "5") (pinfunction "5_5") (pintype "passive"))
      (node (ref "U5") (pin "52") (pinfunction "PTC7_52") (pintype "bidirectional"))
    )
    (net (code "80") (name "/USER25") (class "Default")
      (node (ref "JRIGHT_B") (pin "2") (pinfunction "2_2") (pintype "passive"))
      (node (ref "R11") (pin "1") (pinfunction "1_1") (pintype "passive"))
    )
    (net (code "81") (name "/USER26") (class "Default")
      (node (ref "JRIGHT_C") (pin "4") (pinfunction "4_4") (pintype "passive"))
      (node (ref "U5") (pin "55") (pinfunction "PTC10_55") (pintype "bidirectional"))
    )
    (net (code "82") (name "/USER27") (class "Default")
      (node (ref "JRIGHT_C") (pin "2") (pinfunction "2_2") (pintype "passive"))
      (node (ref "U5") (pin "56") (pinfunction "PTC11_56") (pintype "bidirectional"))
    )
    (net (code "83") (name "/USER28") (class "Default")
      (node (ref "JRIGHT_C") (pin "3") (pinfunction "3_3") (pintype "passive"))
      (node (ref "U5") (pin "57") (pinfunction "PTD0_57") (pintype "bidirectional"))
    )
    (net (code "84") (name "/USER29") (class "Default")
      (node (ref "JLEFT_C") (pin "4") (pinfunction "4_4") (pintype "passive"))
      (node (ref "R12") (pin "1") (pinfunction "1_1") (pintype "passive"))
      (node (ref "U6") (pin "23") (pinfunction "PTC2_23") (pintype "bidirectional"))
    )
    (net (code "85") (name "/USER30") (class "Default")
      (node (ref "JLEFT_C") (pin "2") (pinfunction "2_2") (pintype "passive"))
      (node (ref "U420") (pin "24") (pinfunction "GPIO3$24_24") (pintype "bidirectional"))
    )
    (net (code "86") (name "/USER31") (class "Default")
      (node (ref "JLEFT_C") (pin "3") (pinfunction "3_3") (pintype "passive"))
      (node (ref "U420") (pin "25") (pinfunction "GPIO4$25_25") (pintype "power_in"))
    )
    (net (code "87") (name "/VBATT") (class "Default")
      (node (ref "D5") (pin "ANODE") (pinfunction "ANODE_ANODE") (pintype "bidirectional"))
      (node (ref "F3") (pin "1") (pinfunction "P$1_1") (pintype "bidirectional"))
      (node (ref "J2") (pin "1") (pinfunction "1_1") (pintype "bidirectional"))
      (node (ref "J20") (pin "BAT") (pinfunction "BAT_BAT") (pintype "bidirectional"))
      (node (ref "J9") (pin "3") (pinfunction "3_3") (pintype "bidirectional"))
      (node (ref "JRIGHT_A") (pin "6") (pinfunction "6_6") (pintype "passive"))
      (node (ref "L2") (pin "1") (pinfunction "P$1_1") (pintype "bidirectional"))
      (node (ref "R13") (pin "2") (pinfunction "2_2") (pintype "passive"))
      (node (ref "R27") (pin "1") (pinfunction "1_1") (pintype "passive"))
      (node (ref "R71") (pin "1") (pinfunction "1_1") (pintype "passive"))
      (node (ref "TP13") (pin "TP") (pinfunction "TP_TP") (pintype "input"))
    )
    (net (code "88") (name "/VBATT_+3.3V") (class "Default")
      (node (ref "C33") (pin "1") (pinfunction "1_1") (pintype "passive"))
      (node (ref "C34") (pin "1") (pinfunction "1_1") (pintype "passive"))
      (node (ref "R71") (pin "2") (pinfunction "2_2") (pintype "passive"))
      (node (ref "U2") (pin "10") (pinfunction "VIN_10") (pintype "bidirectional"))
      (node (ref "U2") (pin "11") (pinfunction "VIN_11") (pintype "bidirectional"))
    )
    (net (code "89") (name "/VBATT_OUT") (class "Default")
      (node (ref "C21") (pin "1") (pinfunction "1_1") (pintype "passive"))
      (node (ref "F3") (pin "2") (pinfunction "P$2_2") (pintype "bidirectional"))
      (node (ref "R45") (pin "2") (pinfunction "2_2") (pintype "passive"))
      (node (ref "U1") (pin "10") (pinfunction "VOSNS_10") (pintype "bidirectional"))
      (node (ref "U1") (pin "11") (pinfunction "VOUT_11") (pintype "bidirectional"))
    )
    (net (code "90") (name "/WAKE_M1") (class "Default")
      (node (ref "D7") (pin "ANODE") (pinfunction "ANODE_ANODE") (pintype "bidirectional"))
      (node (ref "R1") (pin "1") (pinfunction "1_1") (pintype "passive"))
      (node (ref "U5") (pin "50") (pinfunction "PTC5_50") (pintype "bidirectional"))
      (node (ref "U6") (pin "28") (pinfunction "PTC7_28") (pintype "bidirectional"))
    )
    (net (code "91") (name "/WAKE_M2") (class "Default")
      (node (ref "R11") (pin "2") (pinfunction "2_2") (pintype "passive"))
      (node (ref "R24") (pin "1") (pinfunction "1_1") (pintype "passive"))
      (node (ref "SW4") (pin "A") (pinfunction "P$1_A") (pintype "bidirectional"))
      (node (ref "SW4") (pin "A2") (pinfunction "P$1_A2") (pintype "bidirectional"))
      (node (ref "U5") (pin "54") (pinfunction "PTC9_54") (pintype "bidirectional"))
      (node (ref "U6") (pin "27") (pinfunction "PTC6_27") (pintype "bidirectional"))
    )
    (net (code "92") (name "GND") (class "Default")
      (node (ref "ANT_UFL") (pin "GND1") (pinfunction "GND1_GND1") (pintype "bidirectional"))
      (node (ref "ANT_UFL") (pin "GND2") (pinfunction "GND2_GND2") (pintype "bidirectional"))
      (node (ref "ANT_UFL") (pin "GND3") (pinfunction "GND3_GND3") (pintype "bidirectional"))
      (node (ref "C1") (pin "2") (pinfunction "2_2") (pintype "passive"))
      (node (ref "C10") (pin "2") (pinfunction "2_2") (pintype "passive"))
      (node (ref "C11") (pin "2") (pinfunction "2_2") (pintype "passive"))
      (node (ref "C12") (pin "2") (pinfunction "2_2") (pintype "passive"))
      (node (ref "C17") (pin "2") (pinfunction "2_2") (pintype "passive"))
      (node (ref "C18") (pin "2") (pinfunction "2_2") (pintype "passive"))
      (node (ref "C19") (pin "2") (pinfunction "2_2") (pintype "passive"))
      (node (ref "C2") (pin "2") (pinfunction "2_2") (pintype "passive"))
      (node (ref "C20") (pin "2") (pinfunction "2_2") (pintype "passive"))
      (node (ref "C21") (pin "2") (pinfunction "2_2") (pintype "passive"))
      (node (ref "C22") (pin "2") (pinfunction "2_2") (pintype "passive"))
      (node (ref "C23") (pin "2") (pinfunction "2_2") (pintype "passive"))
      (node (ref "C24") (pin "2") (pinfunction "2_2") (pintype "passive"))
      (node (ref "C25") (pin "2") (pinfunction "2_2") (pintype "passive"))
      (node (ref "C26") (pin "2") (pinfunction "2_2") (pintype "passive"))
      (node (ref "C27") (pin "1") (pinfunction "C1_1") (pintype "passive"))
      (node (ref "C28") (pin "2") (pinfunction "2_2") (pintype "passive"))
      (node (ref "C29") (pin "2") (pinfunction "2_2") (pintype "passive"))
      (node (ref "C3") (pin "2") (pinfunction "2_2") (pintype "passive"))
      (node (ref "C30") (pin "2") (pinfunction "2_2") (pintype "passive"))
      (node (ref "C31") (pin "2") (pinfunction "2_2") (pintype "passive"))
      (node (ref "C32") (pin "2") (pinfunction "2_2") (pintype "passive"))
      (node (ref "C33") (pin "2") (pinfunction "2_2") (pintype "passive"))
      (node (ref "C34") (pin "2") (pinfunction "2_2") (pintype "passive"))
      (node (ref "C35") (pin "2") (pinfunction "2_2") (pintype "passive"))
      (node (ref "C36") (pin "2") (pinfunction "2_2") (pintype "passive"))
      (node (ref "C37") (pin "2") (pinfunction "2_2") (pintype "passive"))
      (node (ref "C38") (pin "2") (pinfunction "2_2") (pintype "passive"))
      (node (ref "C39") (pin "1") (pinfunction "1_1") (pintype "passive"))
      (node (ref "C4") (pin "2") (pinfunction "2_2") (pintype "passive"))
      (node (ref "C40") (pin "1") (pinfunction "1_1") (pintype "passive"))
      (node (ref "C41") (pin "2") (pinfunction "2_2") (pintype "passive"))
      (node (ref "C42") (pin "2") (pinfunction "2_2") (pintype "passive"))
      (node (ref "C43") (pin "2") (pinfunction "2_2") (pintype "passive"))
      (node (ref "C44") (pin "2") (pinfunction "2_2") (pintype "passive"))
      (node (ref "C45") (pin "2") (pinfunction "2_2") (pintype "passive"))
      (node (ref "C46") (pin "1") (pinfunction "1_1") (pintype "passive"))
      (node (ref "C47") (pin "2") (pinfunction "2_2") (pintype "passive"))
      (node (ref "C48") (pin "2") (pinfunction "2_2") (pintype "passive"))
      (node (ref "C5") (pin "2") (pinfunction "2_2") (pintype "passive"))
      (node (ref "C51") (pin "2") (pinfunction "2_2") (pintype "passive"))
      (node (ref "C6") (pin "1") (pinfunction "1_1") (pintype "passive"))
      (node (ref "C7") (pin "2") (pinfunction "2_2") (pintype "passive"))
      (node (ref "C8") (pin "2") (pinfunction "2_2") (pintype "passive"))
      (node (ref "C9") (pin "2") (pinfunction "2_2") (pintype "passive"))
      (node (ref "J1") (pin "GND") (pinfunction "GND_GND") (pintype "bidirectional"))
      (node (ref "J1") (pin "GND$1") (pinfunction "GND_GND$1") (pintype "bidirectional"))
      (node (ref "J1") (pin "GND$2") (pinfunction "GND_GND$2") (pintype "bidirectional"))
      (node (ref "J1") (pin "GND$3") (pinfunction "GND_GND$3") (pintype "bidirectional"))
      (node (ref "J1") (pin "GND$4") (pinfunction "GND_GND$4") (pintype "bidirectional"))
      (node (ref "J1") (pin "GND$5") (pinfunction "GND_GND$5") (pintype "bidirectional"))
      (node (ref "J1") (pin "GND$6") (pinfunction "GND_GND$6") (pintype "bidirectional"))
      (node (ref "J20") (pin "CHASSIS1") (pinfunction "CHASSIS_1_CHASSIS1") (pintype "bidirectional"))
      (node (ref "J20") (pin "CHASSIS2") (pinfunction "CHASSIS_2_CHASSIS2") (pintype "bidirectional"))
      (node (ref "J20") (pin "GND") (pinfunction "GND_GND") (pintype "bidirectional"))
      (node (ref "JLEFT_A") (pin "5") (pinfunction "5_5") (pintype "passive"))
      (node (ref "JRIGHT_A") (pin "5") (pinfunction "5_5") (pintype "passive"))
      (node (ref "L3") (pin "2") (pinfunction "P$2_2") (pintype "bidirectional"))
      (node (ref "R2000") (pin "1") (pinfunction "1_1") (pintype "passive"))
      (node (ref "R26") (pin "2") (pinfunction "2_2") (pintype "passive"))
      (node (ref "R28") (pin "1") (pinfunction "1_1") (pintype "passive"))
      (node (ref "R3") (pin "2") (pinfunction "2_2") (pintype "passive"))
      (node (ref "R41") (pin "2") (pinfunction "2_2") (pintype "passive"))
      (node (ref "R46") (pin "1") (pinfunction "1_1") (pintype "passive"))
      (node (ref "R65") (pin "2") (pinfunction "2_2") (pintype "passive"))
      (node (ref "R7") (pin "1") (pinfunction "1_1") (pintype "passive"))
      (node (ref "R70") (pin "1") (pinfunction "1_1") (pintype "passive"))
      (node (ref "R8") (pin "1") (pinfunction "1_1") (pintype "passive"))
      (node (ref "R9") (pin "1") (pinfunction "1_1") (pintype "passive"))
      (node (ref "SIM1") (pin "C5") (pinfunction "GND_C5") (pintype "bidirectional"))
      (node (ref "SW1") (pin "B") (pinfunction "P$2_B") (pintype "bidirectional"))
      (node (ref "SW1") (pin "B2") (pinfunction "P$2_B2") (pintype "bidirectional"))
      (node (ref "SW3") (pin "B") (pinfunction "P$2_B") (pintype "bidirectional"))
      (node (ref "SW3") (pin "B2") (pinfunction "P$2_B2") (pintype "bidirectional"))
      (node (ref "SW4") (pin "B") (pinfunction "P$2_B") (pintype "bidirectional"))
      (node (ref "SW4") (pin "B2") (pinfunction "P$2_B2") (pintype "bidirectional"))
      (node (ref "TP20") (pin "TP") (pinfunction "TP_TP") (pintype "input"))
      (node (ref "U1") (pin "6") (pinfunction "GND_6") (pintype "bidirectional"))
      (node (ref "U1") (pin "PAD") (pinfunction "GND_PAD") (pintype "bidirectional"))
      (node (ref "U19") (pin "1") (pinfunction "CTG_1") (pintype "bidirectional"))
      (node (ref "U19") (pin "4") (pinfunction "GND_4") (pintype "bidirectional"))
      (node (ref "U19") (pin "6") (pinfunction "QST_6") (pintype "bidirectional"))
      (node (ref "U19") (pin "EP") (pinfunction "GND_EP") (pintype "bidirectional"))
      (node (ref "U2") (pin "2") (pinfunction "GND_2") (pintype "bidirectional"))
      (node (ref "U2") (pin "POWERPAD") (pinfunction "PGND_POWERPAD") (pintype "bidirectional"))
      (node (ref "U3") (pin "4") (pinfunction "VSS_4") (pintype "bidirectional"))
      (node (ref "U3") (pin "P$9") (pinfunction "VSS_P$9") (pintype "bidirectional"))
      (node (ref "U420") (pin "1") (pinfunction "GND$1_1") (pintype "bidirectional"))
      (node (ref "U420") (pin "10") (pinfunction "RTS$10_10") (pintype "bidirectional"))
      (node (ref "U420") (pin "14") (pinfunction "GND$14_14") (pintype "bidirectional"))
      (node (ref "U420") (pin "20") (pinfunction "GND$20_20") (pintype "bidirectional"))
      (node (ref "U420") (pin "21") (pinfunction "GND$21_21") (pintype "bidirectional"))
      (node (ref "U420") (pin "22") (pinfunction "GND$22_22") (pintype "power_in"))
      (node (ref "U420") (pin "3") (pinfunction "GND$3_3") (pintype "bidirectional"))
      (node (ref "U420") (pin "30") (pinfunction "GND$30_30") (pintype "bidirectional"))
      (node (ref "U420") (pin "32") (pinfunction "GND$32_32") (pintype "power_in"))
      (node (ref "U420") (pin "33") (pinfunction "RSVD$33_33") (pintype "power_in"))
      (node (ref "U420") (pin "43") (pinfunction "GND$43_43") (pintype "bidirectional"))
      (node (ref "U420") (pin "5") (pinfunction "GND$5_5") (pintype "bidirectional"))
      (node (ref "U420") (pin "50") (pinfunction "GND$50_50") (pintype "bidirectional"))
      (node (ref "U420") (pin "54") (pinfunction "GND$54_54") (pintype "power_in"))
      (node (ref "U420") (pin "55") (pinfunction "GND$55_55") (pintype "power_in"))
      (node (ref "U420") (pin "57") (pinfunction "GND$57_57") (pintype "power_in"))
      (node (ref "U420") (pin "58") (pinfunction "GND$58_58") (pintype "power_in"))
      (node (ref "U420") (pin "59") (pinfunction "GND$59_59") (pintype "power_in"))
      (node (ref "U420") (pin "60") (pinfunction "GND$60_60") (pintype "power_in"))
      (node (ref "U420") (pin "61") (pinfunction "GND$61_61") (pintype "power_in"))
      (node (ref "U420") (pin "63") (pinfunction "GND$63_63") (pintype "power_in"))
      (node (ref "U420") (pin "64") (pinfunction "GND$64_64") (pintype "power_in"))
      (node (ref "U420") (pin "65") (pinfunction "GND$65_65") (pintype "bidirectional"))
      (node (ref "U420") (pin "66") (pinfunction "GND$66_66") (pintype "bidirectional"))
      (node (ref "U420") (pin "67") (pinfunction "GND$67_67") (pintype "bidirectional"))
      (node (ref "U420") (pin "68") (pinfunction "GND$68_68") (pintype "bidirectional"))
      (node (ref "U420") (pin "69") (pinfunction "GND$69_69") (pintype "bidirectional"))
      (node (ref "U420") (pin "70") (pinfunction "GND$70_70") (pintype "bidirectional"))
      (node (ref "U420") (pin "71") (pinfunction "GND$71_71") (pintype "bidirectional"))
      (node (ref "U420") (pin "72") (pinfunction "GND$72_72") (pintype "bidirectional"))
      (node (ref "U420") (pin "73") (pinfunction "GND$73_73") (pintype "bidirectional"))
      (node (ref "U420") (pin "74") (pinfunction "GND$74_74") (pintype "bidirectional"))
      (node (ref "U420") (pin "75") (pinfunction "GND$75_75") (pintype "bidirectional"))
      (node (ref "U420") (pin "76") (pinfunction "GND$76_76") (pintype "bidirectional"))
      (node (ref "U420") (pin "77") (pinfunction "GND$77_77") (pintype "bidirectional"))
      (node (ref "U420") (pin "78") (pinfunction "GND$78_78") (pintype "bidirectional"))
      (node (ref "U420") (pin "79") (pinfunction "GND$79_79") (pintype "bidirectional"))
      (node (ref "U420") (pin "80") (pinfunction "GND$80_80") (pintype "bidirectional"))
      (node (ref "U420") (pin "81") (pinfunction "GND$81_81") (pintype "bidirectional"))
      (node (ref "U420") (pin "82") (pinfunction "GND$82_82") (pintype "bidirectional"))
      (node (ref "U420") (pin "83") (pinfunction "GND$83_83") (pintype "bidirectional"))
      (node (ref "U420") (pin "84") (pinfunction "GND$84_84") (pintype "bidirectional"))
      (node (ref "U420") (pin "85") (pinfunction "GND$85_85") (pintype "bidirectional"))
      (node (ref "U420") (pin "86") (pinfunction "GND$86_86") (pintype "bidirectional"))
      (node (ref "U420") (pin "87") (pinfunction "GND$87_87") (pintype "bidirectional"))
      (node (ref "U420") (pin "88") (pinfunction "GND$88_88") (pintype "bidirectional"))
      (node (ref "U420") (pin "89") (pinfunction "GND$89_89") (pintype "bidirectional"))
      (node (ref "U420") (pin "9") (pinfunction "DTR$9_9") (pintype "bidirectional"))
      (node (ref "U420") (pin "90") (pinfunction "GND$90_90") (pintype "bidirectional"))
      (node (ref "U420") (pin "91") (pinfunction "GND$91_91") (pintype "bidirectional"))
      (node (ref "U420") (pin "92") (pinfunction "GND$92_92") (pintype "bidirectional"))
      (node (ref "U420") (pin "93") (pinfunction "GND$93_93") (pintype "bidirectional"))
      (node (ref "U420") (pin "94") (pinfunction "GND$94_94") (pintype "bidirectional"))
      (node (ref "U420") (pin "95") (pinfunction "GND$95_95") (pintype "bidirectional"))
      (node (ref "U420") (pin "96") (pinfunction "GND$96_96") (pintype "bidirectional"))
      (node (ref "U5") (pin "31") (pinfunction "VSS_31") (pintype "bidirectional"))
      (node (ref "U5") (pin "4") (pinfunction "VSS_4") (pintype "bidirectional"))
      (node (ref "U5") (pin "47") (pinfunction "VSS_47") (pintype "bidirectional"))
      (node (ref "U6") (pin "16") (pinfunction "VSS_16") (pintype "bidirectional"))
      (node (ref "U6") (pin "8") (pinfunction "VSSA_8") (pintype "bidirectional"))
      (node (ref "U6") (pin "PAD") (pinfunction "VSS_PAD") (pintype "bidirectional"))
      (node (ref "U7") (pin "3") (pinfunction "P$3_3") (pintype "bidirectional"))
      (node (ref "U8") (pin "P$16") (pinfunction "DIR2_P$16") (pintype "input"))
      (node (ref "U8") (pin "P$6") (pinfunction "DIR4_P$6") (pintype "input"))
      (node (ref "U8") (pin "P$7") (pinfunction "~{OE}_P$7") (pintype "input"))
      (node (ref "U8") (pin "P$8") (pinfunction "GND_P$8") (pintype "passive"))
      (node (ref "U9") (pin "3") (pinfunction "P$3_3") (pintype "bidirectional"))
      (node (ref "X1") (pin "GND") (pinfunction "GND_GND") (pintype "bidirectional"))
    )
    (net (code "93") (name "Net-(C27-C2)") (class "Default")
      (node (ref "C27") (pin "2") (pinfunction "C2_2") (pintype "passive"))
      (node (ref "R4") (pin "2") (pinfunction "2_2") (pintype "passive"))
      (node (ref "U19") (pin "3") (pinfunction "VDD_3") (pintype "bidirectional"))
    )
    (net (code "94") (name "Net-(D1-PadCATHODE)") (class "Default")
      (node (ref "D1") (pin "CATHODE") (pinfunction "CATHODE_CATHODE") (pintype "bidirectional"))
      (node (ref "R26") (pin "1") (pinfunction "1_1") (pintype "passive"))
    )
    (net (code "95") (name "Net-(D3-PadCATHODE)") (class "Default")
      (node (ref "D3") (pin "CATHODE") (pinfunction "CATHODE_CATHODE") (pintype "bidirectional"))
      (node (ref "R3") (pin "1") (pinfunction "1_1") (pintype "passive"))
    )
    (net (code "96") (name "Net-(D5-PadCATHODE)") (class "Default")
      (node (ref "D5") (pin "CATHODE") (pinfunction "CATHODE_CATHODE") (pintype "bidirectional"))
      (node (ref "R41") (pin "1") (pinfunction "1_1") (pintype "passive"))
    )
    (net (code "97") (name "Net-(D7-PadCATHODE)") (class "Default")
      (node (ref "D7") (pin "CATHODE") (pinfunction "CATHODE_CATHODE") (pintype "bidirectional"))
      (node (ref "R65") (pin "1") (pinfunction "1_1") (pintype "passive"))
    )
    (net (code "98") (name "Net-(L1-P$1)") (class "Default")
      (node (ref "C10") (pin "1") (pinfunction "1_1") (pintype "passive"))
      (node (ref "C8") (pin "1") (pinfunction "1_1") (pintype "passive"))
      (node (ref "L1") (pin "1") (pinfunction "P$1_1") (pintype "bidirectional"))
      (node (ref "R16") (pin "2") (pinfunction "2_2") (pintype "passive"))
      (node (ref "U5") (pin "3") (pinfunction "VDD_3") (pintype "bidirectional"))
    )
    (net (code "99") (name "Net-(L1-P$2)") (class "Default")
      (node (ref "C13") (pin "1") (pinfunction "1_1") (pintype "passive"))
      (node (ref "L1") (pin "2") (pinfunction "P$2_2") (pintype "bidirectional"))
      (node (ref "R19") (pin "1") (pinfunction "1_1") (pintype "passive"))
      (node (ref "U5") (pin "13") (pinfunction "VDDA_13") (pintype "bidirectional"))
    )
    (net (code "100") (name "Net-(L2-P$2)") (class "Default")
      (node (ref "L2") (pin "2") (pinfunction "P$2_2") (pintype "bidirectional"))
      (node (ref "U4") (pin "1") (pinfunction "A1_1") (pintype "bidirectional"))
      (node (ref "U4") (pin "2") (pinfunction "A2_2") (pintype "bidirectional"))
    )
    (net (code "101") (name "Net-(L5-PadP$1)") (class "Default")
      (node (ref "L5") (pin "P$1") (pinfunction "P$1_P$1") (pintype "bidirectional"))
      (node (ref "U2") (pin "8") (pinfunction "L1_8") (pintype "bidirectional"))
      (node (ref "U2") (pin "9") (pinfunction "L1_9") (pintype "bidirectional"))
    )
    (net (code "102") (name "Net-(L5-PadP$2)") (class "Default")
      (node (ref "L5") (pin "P$2") (pinfunction "P$2_P$2") (pintype "bidirectional"))
      (node (ref "U2") (pin "6") (pinfunction "L2_6") (pintype "bidirectional"))
      (node (ref "U2") (pin "7") (pinfunction "L2_7") (pintype "bidirectional"))
    )
    (net (code "103") (name "Net-(R67-Pad1)") (class "Default")
      (node (ref "R67") (pin "1") (pinfunction "1_1") (pintype "passive"))
      (node (ref "R69") (pin "2") (pinfunction "2_2") (pintype "passive"))
      (node (ref "U2") (pin "4") (pinfunction "VOUT_4") (pintype "bidirectional"))
      (node (ref "U2") (pin "5") (pinfunction "VOUT_5") (pintype "bidirectional"))
    )
    (net (code "104") (name "Net-(U1-IAC)") (class "Default")
      (node (ref "R8") (pin "2") (pinfunction "2_2") (pintype "passive"))
      (node (ref "U1") (pin "16") (pinfunction "IAC_16") (pintype "bidirectional"))
    )
    (net (code "105") (name "Net-(U1-IEND)") (class "Default")
      (node (ref "R9") (pin "2") (pinfunction "2_2") (pintype "passive"))
      (node (ref "U1") (pin "13") (pinfunction "IEND_13") (pintype "bidirectional"))
    )
    (net (code "106") (name "Net-(U1-ISEL)") (class "Default")
      (node (ref "J2") (pin "3") (pinfunction "3_3") (pintype "bidirectional"))
      (node (ref "R15") (pin "2") (pinfunction "2_2") (pintype "passive"))
      (node (ref "R6") (pin "2") (pinfunction "2_2") (pintype "passive"))
      (node (ref "U1") (pin "1") (pinfunction "VIN_1") (pintype "bidirectional"))
      (node (ref "U1") (pin "2") (pinfunction "VINSNS_2") (pintype "bidirectional"))
      (node (ref "U1") (pin "9") (pinfunction "ISEL_9") (pintype "bidirectional"))
    )
    (net (code "107") (name "Net-(U1-IUSB)") (class "Default")
      (node (ref "R7") (pin "2") (pinfunction "2_2") (pintype "passive"))
      (node (ref "U1") (pin "15") (pinfunction "IUSB_15") (pintype "bidirectional"))
    )
    (net (code "108") (name "Net-(U1-MODE)") (class "Default")
      (node (ref "R15") (pin "1") (pinfunction "1_1") (pintype "passive"))
      (node (ref "R28") (pin "2") (pinfunction "2_2") (pintype "passive"))
      (node (ref "U1") (pin "14") (pinfunction "MODE_14") (pintype "bidirectional"))
    )
    (net (code "109") (name "Net-(U1-SD)") (class "Default")
      (node (ref "R46") (pin "2") (pinfunction "2_2") (pintype "passive"))
      (node (ref "U1") (pin "7") (pinfunction "SD_7") (pintype "bidirectional"))
    )
    (net (code "110") (name "Net-(U1-TH)") (class "Default")
      (node (ref "R10") (pin "1") (pinfunction "1_1") (pintype "passive"))
      (node (ref "R2000") (pin "2") (pinfunction "2_2") (pintype "passive"))
      (node (ref "U1") (pin "8") (pinfunction "TH_8") (pintype "bidirectional"))
    )
    (net (code "111") (name "Net-(U1-TPRG)") (class "Default")
      (node (ref "C22") (pin "1") (pinfunction "1_1") (pintype "passive"))
      (node (ref "U1") (pin "5") (pinfunction "TPRG_5") (pintype "bidirectional"))
    )
    (net (code "112") (name "Net-(U1-VREF)") (class "Default")
      (node (ref "C5") (pin "1") (pinfunction "1_1") (pintype "passive"))
      (node (ref "R10") (pin "2") (pinfunction "2_2") (pintype "passive"))
      (node (ref "U1") (pin "12") (pinfunction "VREF_12") (pintype "bidirectional"))
    )
    (net (code "113") (name "Net-(U2-EN)") (class "Default")
      (node (ref "C48") (pin "1") (pinfunction "1_1") (pintype "passive"))
      (node (ref "U2") (pin "1") (pinfunction "VINA_1") (pintype "bidirectional"))
      (node (ref "U2") (pin "12") (pinfunction "EN_12") (pintype "bidirectional"))
      (node (ref "U2") (pin "13") (pinfunction "PS/SYNC_13") (pintype "bidirectional"))
    )
    (net (code "114") (name "Net-(U2-FB)") (class "Default")
      (node (ref "R69") (pin "1") (pinfunction "1_1") (pintype "passive"))
      (node (ref "R70") (pin "2") (pinfunction "2_2") (pintype "passive"))
      (node (ref "U2") (pin "3") (pinfunction "FB_3") (pintype "bidirectional"))
    )
    (net (code "115") (name "Net-(U3-VDD)") (class "Default")
      (node (ref "C19") (pin "1") (pinfunction "1_1") (pintype "passive"))
      (node (ref "R2") (pin "1") (pinfunction "1_1") (pintype "passive"))
      (node (ref "U3") (pin "3") (pinfunction "~{WP}_3") (pintype "bidirectional"))
      (node (ref "U3") (pin "7") (pinfunction "~{HOLD}_7") (pintype "bidirectional"))
      (node (ref "U3") (pin "8") (pinfunction "VDD_8") (pintype "bidirectional"))
    )
    (net (code "116") (name "Net-(U4-C)") (class "Default")
      (node (ref "C18") (pin "1") (pinfunction "1_1") (pintype "passive"))
      (node (ref "U4") (pin "3") (pinfunction "C_3") (pintype "bidirectional"))
      (node (ref "U5") (pin "8") (pinfunction "VREGIN_8") (pintype "bidirectional"))
    )
    (net (code "117") (name "Net-(U5-EXTAL32)") (class "Default")
      (node (ref "C17") (pin "1") (pinfunction "1_1") (pintype "passive"))
      (node (ref "R38") (pin "1") (pinfunction "1_1") (pintype "passive"))
      (node (ref "U5") (pin "20") (pinfunction "EXTAL32_20") (pintype "bidirectional"))
      (node (ref "X2") (pin "P$1") (pinfunction "XTAL1_P$1") (pintype "bidirectional"))
    )
    (net (code "118") (name "Net-(U5-PTA18)") (class "Default")
      (node (ref "C30") (pin "1") (pinfunction "1_1") (pintype "passive"))
      (node (ref "R5") (pin "2") (pinfunction "2_2") (pintype "passive"))
      (node (ref "U5") (pin "32") (pinfunction "PTA18_32") (pintype "bidirectional"))
      (node (ref "X1") (pin "XTAL1") (pinfunction "XTAL1_XTAL1") (pintype "bidirectional"))
    )
    (net (code "119") (name "Net-(U5-PTA19)") (class "Default")
      (node (ref "C31") (pin "1") (pinfunction "1_1") (pintype "passive"))
      (node (ref "R5") (pin "1") (pinfunction "1_1") (pintype "passive"))
      (node (ref "U5") (pin "33") (pinfunction "PTA19_33") (pintype "bidirectional"))
      (node (ref "X1") (pin "XTAL2") (pinfunction "XTAL2_XTAL2") (pintype "bidirectional"))
    )
    (net (code "120") (name "Net-(U5-VBAT)") (class "Default")
      (node (ref "C9") (pin "1") (pinfunction "1_1") (pintype "passive"))
      (node (ref "R21") (pin "2") (pinfunction "2_2") (pintype "passive"))
      (node (ref "U5") (pin "21") (pinfunction "VBAT_21") (pintype "bidirectional"))
    )
    (net (code "121") (name "Net-(U5-VDD1)") (class "Default")
      (node (ref "C7") (pin "1") (pinfunction "1_1") (pintype "passive"))
      (node (ref "R17") (pin "2") (pinfunction "2_2") (pintype "passive"))
      (node (ref "U5") (pin "30") (pinfunction "VDD1_30") (pintype "bidirectional"))
    )
    (net (code "122") (name "Net-(U5-VDD2)") (class "Default")
      (node (ref "C4") (pin "1") (pinfunction "1_1") (pintype "passive"))
      (node (ref "R18") (pin "2") (pinfunction "2_2") (pintype "passive"))
      (node (ref "U5") (pin "48") (pinfunction "VDD2_48") (pintype "bidirectional"))
    )
    (net (code "123") (name "Net-(U5-VOUT33)") (class "Default")
      (node (ref "R20") (pin "2") (pinfunction "2_2") (pintype "passive"))
      (node (ref "U5") (pin "7") (pinfunction "VOUT33_7") (pintype "bidirectional"))
    )
    (net (code "124") (name "Net-(U5-VREF_OUT)") (class "Default")
      (node (ref "C15") (pin "1") (pinfunction "1_1") (pintype "passive"))
      (node (ref "U5") (pin "17") (pinfunction "VREF_OUT_17") (pintype "bidirectional"))
    )
    (net (code "125") (name "Net-(U5-XTAL32)") (class "Default")
      (node (ref "C23") (pin "1") (pinfunction "1_1") (pintype "passive"))
      (node (ref "R38") (pin "2") (pinfunction "2_2") (pintype "passive"))
      (node (ref "U5") (pin "19") (pinfunction "XTAL32_19") (pintype "bidirectional"))
      (node (ref "X2") (pin "P$2") (pinfunction "XTAL2_P$2") (pintype "bidirectional"))
    )
    (net (code "126") (name "Net-(U6-PTA18)") (class "Default")
      (node (ref "C29") (pin "1") (pinfunction "1_1") (pintype "passive"))
      (node (ref "R39") (pin "2") (pinfunction "2_2") (pintype "passive"))
      (node (ref "U6") (pin "17") (pinfunction "PTA18_17") (pintype "bidirectional"))
      (node (ref "X3") (pin "P$2") (pinfunction "XTAL2_P$2") (pintype "bidirectional"))
    )
    (net (code "127") (name "Net-(U6-PTA19)") (class "Default")
      (node (ref "C32") (pin "1") (pinfunction "1_1") (pintype "passive"))
      (node (ref "R39") (pin "1") (pinfunction "1_1") (pintype "passive"))
      (node (ref "U6") (pin "18") (pinfunction "PTA19_18") (pintype "bidirectional"))
      (node (ref "X3") (pin "P$1") (pinfunction "XTAL1_P$1") (pintype "bidirectional"))
    )
    (net (code "128") (name "Net-(U6-PTB0)") (class "Default")
      (node (ref "R58") (pin "1") (pinfunction "1_1") (pintype "passive"))
      (node (ref "U6") (pin "20") (pinfunction "PTB0_20") (pintype "bidirectional"))
    )
    (net (code "129") (name "Net-(U6-PTB1)") (class "Default")
      (node (ref "R59") (pin "1") (pinfunction "1_1") (pintype "passive"))
      (node (ref "U6") (pin "21") (pinfunction "PTB1_21") (pintype "bidirectional"))
    )
    (net (code "130") (name "Net-(U6-PTC1)") (class "Default")
      (node (ref "R14") (pin "1") (pinfunction "1_1") (pintype "passive"))
      (node (ref "U6") (pin "22") (pinfunction "PTC1_22") (pintype "bidirectional"))
    )
    (net (code "131") (name "Net-(U6-PTC3)") (class "Default")
      (node (ref "R61") (pin "2") (pinfunction "2_2") (pintype "passive"))
      (node (ref "U6") (pin "24") (pinfunction "PTC3_24") (pintype "bidirectional"))
    )
    (net (code "132") (name "Net-(U6-PTC4)") (class "Default")
      (node (ref "R62") (pin "2") (pinfunction "2_2") (pintype "passive"))
      (node (ref "U6") (pin "25") (pinfunction "PTC4_25") (pintype "bidirectional"))
    )
    (net (code "133") (name "Net-(U6-PTD6)") (class "Default")
      (node (ref "R63") (pin "2") (pinfunction "2_2") (pintype "passive"))
      (node (ref "U6") (pin "31") (pinfunction "PTD6_31") (pintype "bidirectional"))
    )
    (net (code "134") (name "Net-(U6-PTD7)") (class "Default")
      (node (ref "R64") (pin "2") (pinfunction "2_2") (pintype "passive"))
      (node (ref "U6") (pin "32") (pinfunction "PTD7_32") (pintype "bidirectional"))
    )
    (net (code "135") (name "Net-(U6-PTE16)") (class "Default")
      (node (ref "R55") (pin "1") (pinfunction "1_1") (pintype "passive"))
      (node (ref "U6") (pin "3") (pinfunction "PTE16_3") (pintype "bidirectional"))
    )
    (net (code "136") (name "Net-(U6-PTE17)") (class "Default")
      (node (ref "R54") (pin "1") (pinfunction "1_1") (pintype "passive"))
      (node (ref "U6") (pin "4") (pinfunction "PTE17_4") (pintype "bidirectional"))
    )
    (net (code "137") (name "Net-(U6-PTE18)") (class "Default")
      (node (ref "R57") (pin "1") (pinfunction "1_1") (pintype "passive"))
      (node (ref "U6") (pin "5") (pinfunction "PTE18_5") (pintype "bidirectional"))
    )
    (net (code "138") (name "Net-(U6-PTE19)") (class "Default")
      (node (ref "R56") (pin "1") (pinfunction "1_1") (pintype "passive"))
      (node (ref "U6") (pin "6") (pinfunction "PTE19_6") (pintype "bidirectional"))
    )
    (net (code "139") (name "Net-(U6-VDD)") (class "Default")
      (node (ref "C28") (pin "1") (pinfunction "1_1") (pintype "passive"))
      (node (ref "C3") (pin "1") (pinfunction "1_1") (pintype "passive"))
      (node (ref "R60") (pin "2") (pinfunction "2_2") (pintype "passive"))
      (node (ref "U6") (pin "15") (pinfunction "VDD_15") (pintype "bidirectional"))
      (node (ref "U6") (pin "7") (pinfunction "VDDA_7") (pintype "bidirectional"))
    )
    (net (code "140") (name "Net-(U8-DIR1)") (class "Default")
      (node (ref "C26") (pin "1") (pinfunction "1_1") (pintype "passive"))
      (node (ref "R48") (pin "2") (pinfunction "2_2") (pintype "passive"))
      (node (ref "U8") (pin "P$14") (pinfunction "VCCA_P$14") (pintype "power_in"))
      (node (ref "U8") (pin "P$15") (pinfunction "DIR1_P$15") (pintype "input"))
      (node (ref "U8") (pin "P$5") (pinfunction "DIR3_P$5") (pintype "input"))
    )
    (net (code "141") (name "Net-(U8-VCCB)") (class "Default")
      (node (ref "C25") (pin "1") (pinfunction "1_1") (pintype "passive"))
      (node (ref "R49") (pin "2") (pinfunction "2_2") (pintype "passive"))
      (node (ref "U8") (pin "P$13") (pinfunction "VCCB_P$13") (pintype "power_in"))
    )
    (net (code "142") (name "Net-(U19-CELL)") (class "Default")
      (node (ref "C20") (pin "1") (pinfunction "1_1") (pintype "passive"))
      (node (ref "R45") (pin "1") (pinfunction "1_1") (pintype "passive"))
      (node (ref "U19") (pin "2") (pinfunction "CELL_2") (pintype "bidirectional"))
    )
    (net (code "143") (name "unconnected-(R23-Pad1)") (class "Default")
      (node (ref "R23") (pin "1") (pinfunction "1_1") (pintype "passive"))
    )
    (net (code "144") (name "unconnected-(R32-Pad2)") (class "Default")
      (node (ref "R32") (pin "2") (pinfunction "2_2") (pintype "passive"))
    )
    (net (code "145") (name "unconnected-(SIM1-NC1-PadMTG1)") (class "Default")
      (node (ref "SIM1") (pin "MTG1") (pinfunction "NC1_MTG1") (pintype "bidirectional"))
    )
    (net (code "146") (name "unconnected-(SIM1-NC2-PadMTG2)") (class "Default")
      (node (ref "SIM1") (pin "MTG2") (pinfunction "NC2_MTG2") (pintype "bidirectional"))
    )
    (net (code "147") (name "unconnected-(U1-ST1-Pad4)") (class "Default")
      (node (ref "U1") (pin "4") (pinfunction "ST1_4") (pintype "bidirectional"))
    )
    (net (code "148") (name "unconnected-(U1-ST2-Pad3)") (class "Default")
      (node (ref "U1") (pin "3") (pinfunction "ST2_3") (pintype "bidirectional"))
    )
    (net (code "149") (name "unconnected-(U5-PGA0_DM-Pad10)") (class "Default")
      (node (ref "U5") (pin "10") (pinfunction "PGA0_DM_10") (pintype "bidirectional"))
    )
    (net (code "150") (name "unconnected-(U5-PGA1_DP-Pad11)") (class "Default")
      (node (ref "U5") (pin "11") (pinfunction "PGA1_DP_11") (pintype "bidirectional"))
    )
    (net (code "151") (name "unconnected-(U5-PTB17-Pad40)") (class "Default")
      (node (ref "U5") (pin "40") (pinfunction "PTB17_40") (pintype "bidirectional"))
    )
    (net (code "152") (name "unconnected-(U6-DAC0_OUT_PTE_30-Pad9)") (class "Default")
      (node (ref "U6") (pin "9") (pinfunction "DAC0_OUT_PTE_30_9") (pintype "bidirectional"))
    )
    (net (code "153") (name "unconnected-(U6-PTA2-Pad12)") (class "Default")
      (node (ref "U6") (pin "12") (pinfunction "PTA2_12") (pintype "bidirectional"))
    )
    (net (code "154") (name "unconnected-(U6-PTA4-Pad14)") (class "Default")
      (node (ref "U6") (pin "14") (pinfunction "PTA4_14") (pintype "bidirectional"))
    )
    (net (code "155") (name "unconnected-(U8-A3-PadP$3)") (class "Default")
      (node (ref "U8") (pin "P$3") (pinfunction "A3_P$3") (pintype "bidirectional"))
    )
    (net (code "156") (name "unconnected-(U8-A4-PadP$4)") (class "Default")
      (node (ref "U8") (pin "P$4") (pinfunction "A4_P$4") (pintype "bidirectional"))
    )
    (net (code "157") (name "unconnected-(U8-B3-PadP$10)") (class "Default")
      (node (ref "U8") (pin "P$10") (pinfunction "B3_P$10") (pintype "bidirectional"))
    )
    (net (code "158") (name "unconnected-(U8-B4-PadP$9)") (class "Default")
      (node (ref "U8") (pin "P$9") (pinfunction "B4_P$9") (pintype "bidirectional"))
    )
    (net (code "159") (name "unconnected-(U19-ALT-Pad5)") (class "Default")
      (node (ref "U19") (pin "5") (pinfunction "ALT_5") (pintype "bidirectional"))
    )
    (net (code "160") (name "unconnected-(U420-CODEC_CLK$19-Pad19)") (class "Default")
      (node (ref "U420") (pin "19") (pinfunction "CODEC_CLK$19_19") (pintype "bidirectional"))
    )
    (net (code "161") (name "unconnected-(U420-CTS$11-Pad11)") (class "Default")
      (node (ref "U420") (pin "11") (pinfunction "CTS$11_11") (pintype "bidirectional"))
    )
    (net (code "162") (name "unconnected-(U420-DCD$8-Pad8)") (class "Default")
      (node (ref "U420") (pin "8") (pinfunction "DCD$8_8") (pintype "bidirectional"))
    )
    (net (code "163") (name "unconnected-(U420-DSR$6-Pad6)") (class "Default")
      (node (ref "U420") (pin "6") (pinfunction "DSR$6_6") (pintype "bidirectional"))
    )
    (net (code "164") (name "unconnected-(U420-I2S_CLK$36-Pad36)") (class "Default")
      (node (ref "U420") (pin "36") (pinfunction "I2S_CLK$36_36") (pintype "bidirectional"))
    )
    (net (code "165") (name "unconnected-(U420-I2S_RXD$37-Pad37)") (class "Default")
      (node (ref "U420") (pin "37") (pinfunction "I2S_RXD$37_37") (pintype "bidirectional"))
    )
    (net (code "166") (name "unconnected-(U420-RI$7-Pad7)") (class "Default")
      (node (ref "U420") (pin "7") (pinfunction "RI$7_7") (pintype "bidirectional"))
    )
    (net (code "167") (name "unconnected-(U420-RSVD$44-Pad44)") (class "Default")
      (node (ref "U420") (pin "44") (pinfunction "RSVD$44_44") (pintype "bidirectional"))
    )
    (net (code "168") (name "unconnected-(U420-RSVD$45-Pad45)") (class "Default")
      (node (ref "U420") (pin "45") (pinfunction "RSVD$45_45") (pintype "bidirectional"))
    )
    (net (code "169") (name "unconnected-(U420-RSVD$46-Pad46)") (class "Default")
      (node (ref "U420") (pin "46") (pinfunction "RSVD$46_46") (pintype "bidirectional"))
    )
    (net (code "170") (name "unconnected-(U420-RSVD$47-Pad47)") (class "Default")
      (node (ref "U420") (pin "47") (pinfunction "RSVD$47_47") (pintype "bidirectional"))
    )
    (net (code "171") (name "unconnected-(U420-RSVD$48-Pad48)") (class "Default")
      (node (ref "U420") (pin "48") (pinfunction "RSVD$48_48") (pintype "bidirectional"))
    )
    (net (code "172") (name "unconnected-(U420-RSVD$49-Pad49)") (class "Default")
      (node (ref "U420") (pin "49") (pinfunction "RSVD$49_49") (pintype "bidirectional"))
    )
    (net (code "173") (name "unconnected-(U420-SIM_DET$42-Pad42)") (class "Default")
      (node (ref "U420") (pin "42") (pinfunction "SIM_DET$42_42") (pintype "bidirectional"))
    )
  )
)
